# Display.net
KiCad netlist of a schematic drawn in Altium Designer
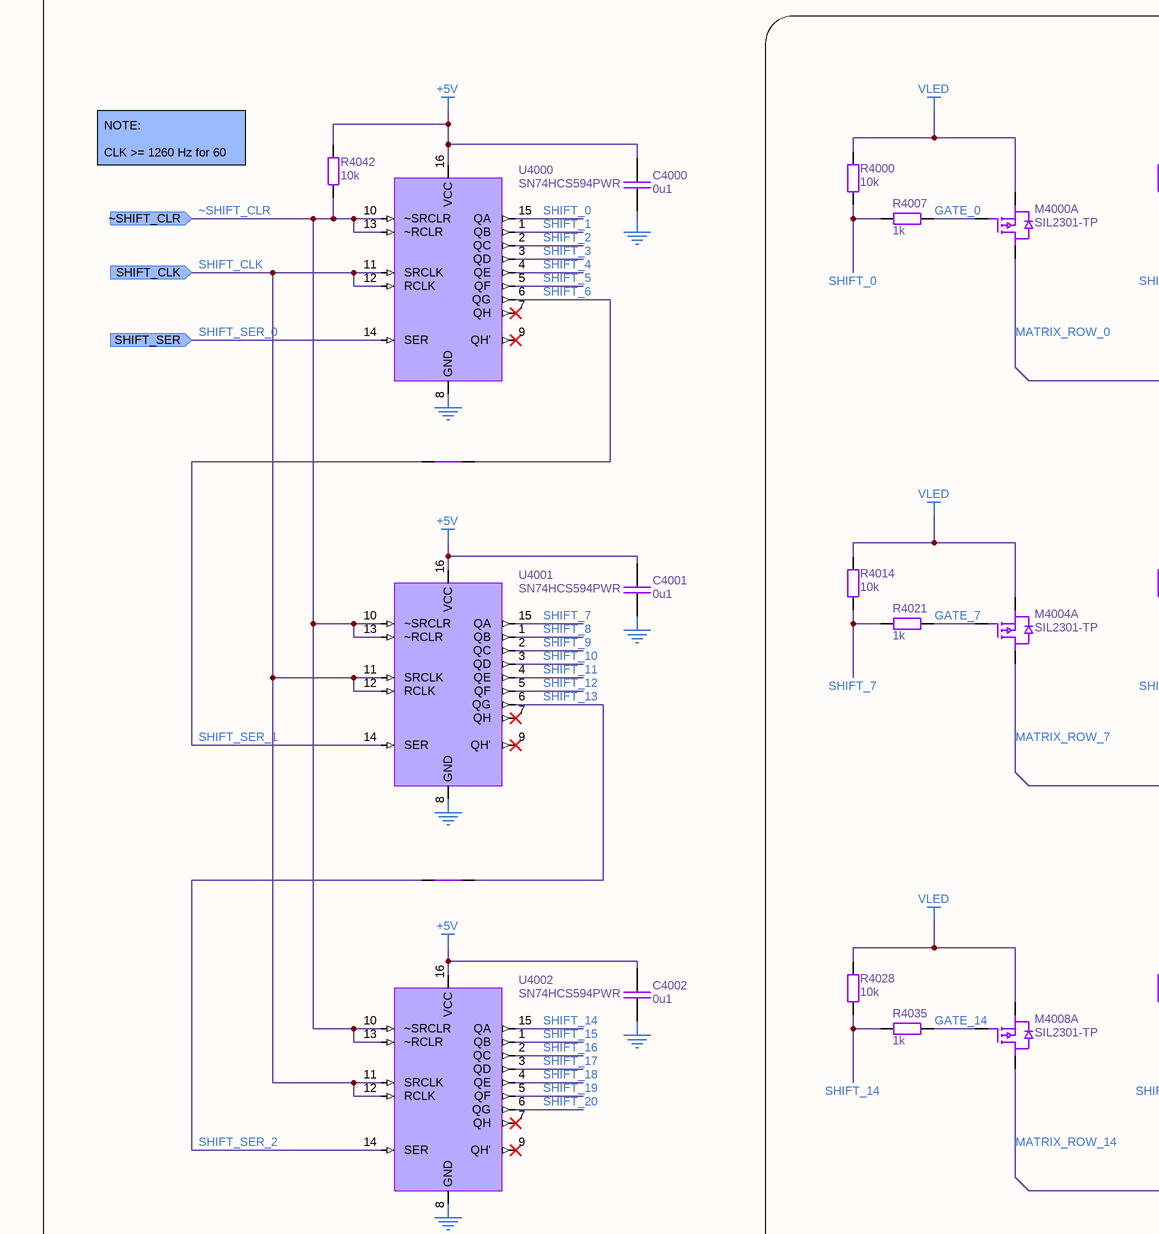
[diagram p0: Display.SchDoc, top left]
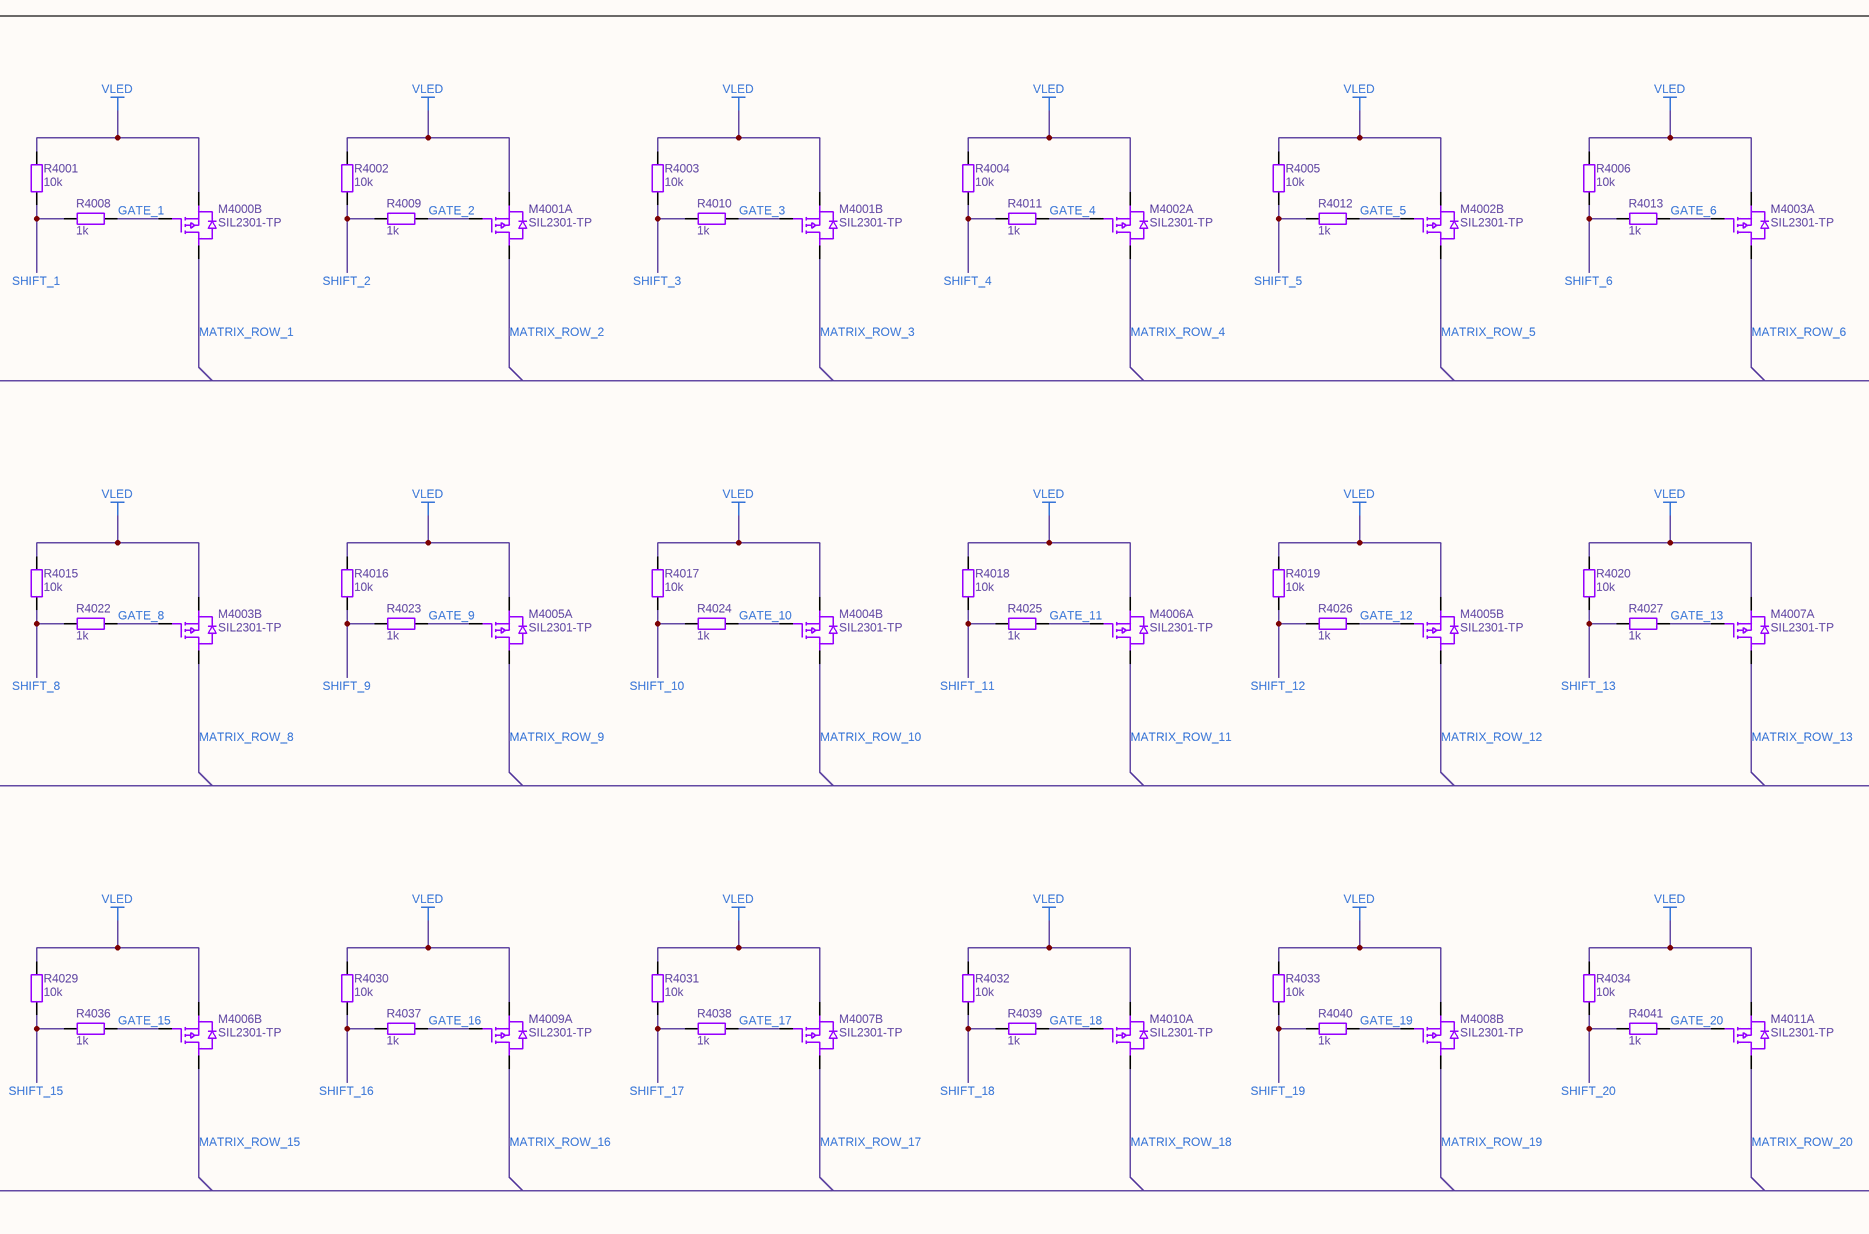
[diagram p1: Display.SchDoc, top middle]
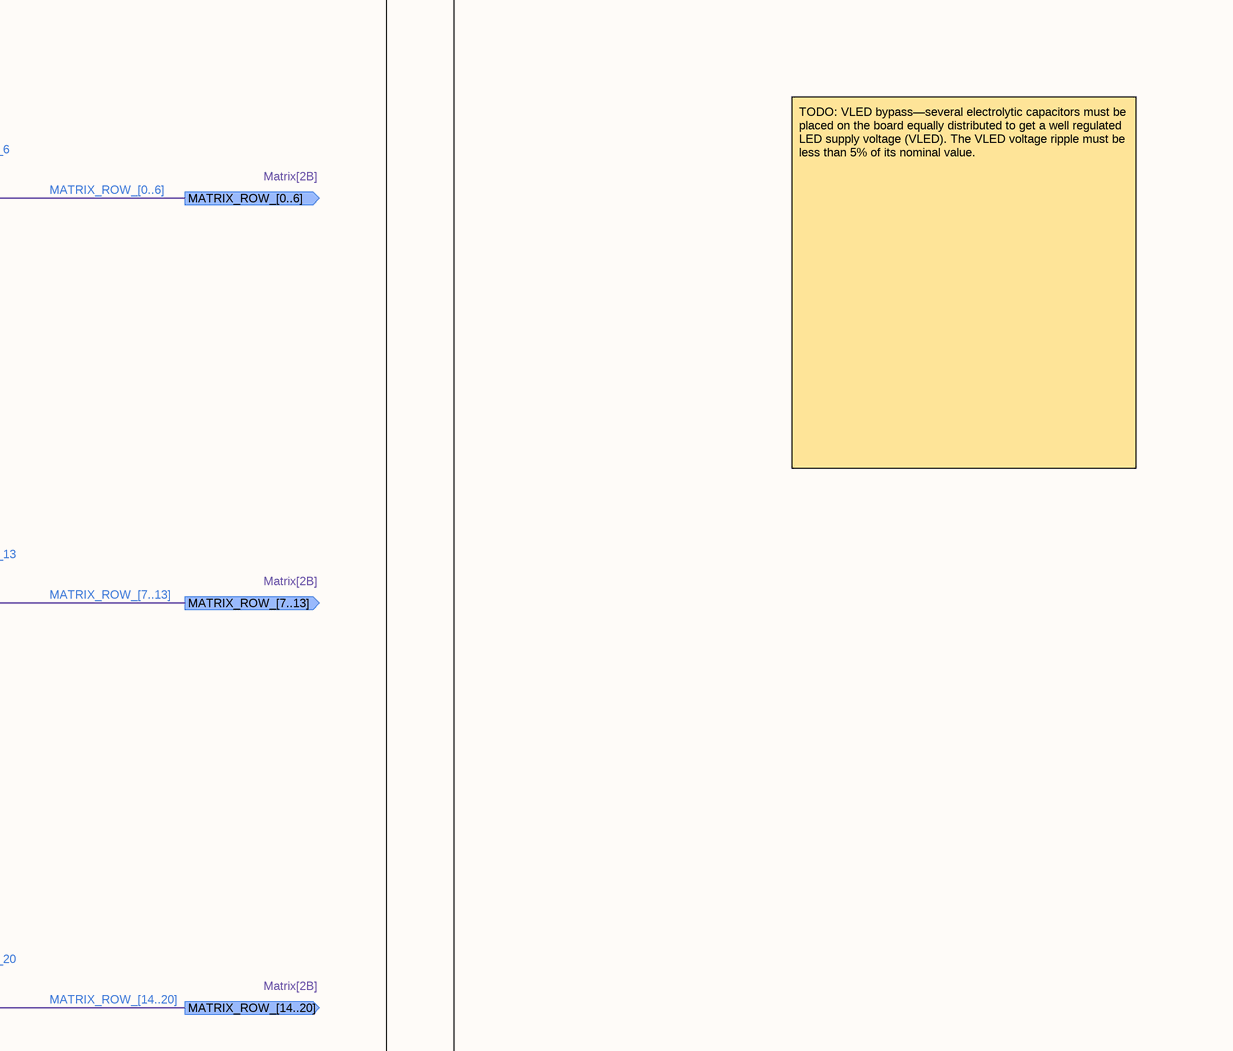
[diagram p2: Display.SchDoc, top right]
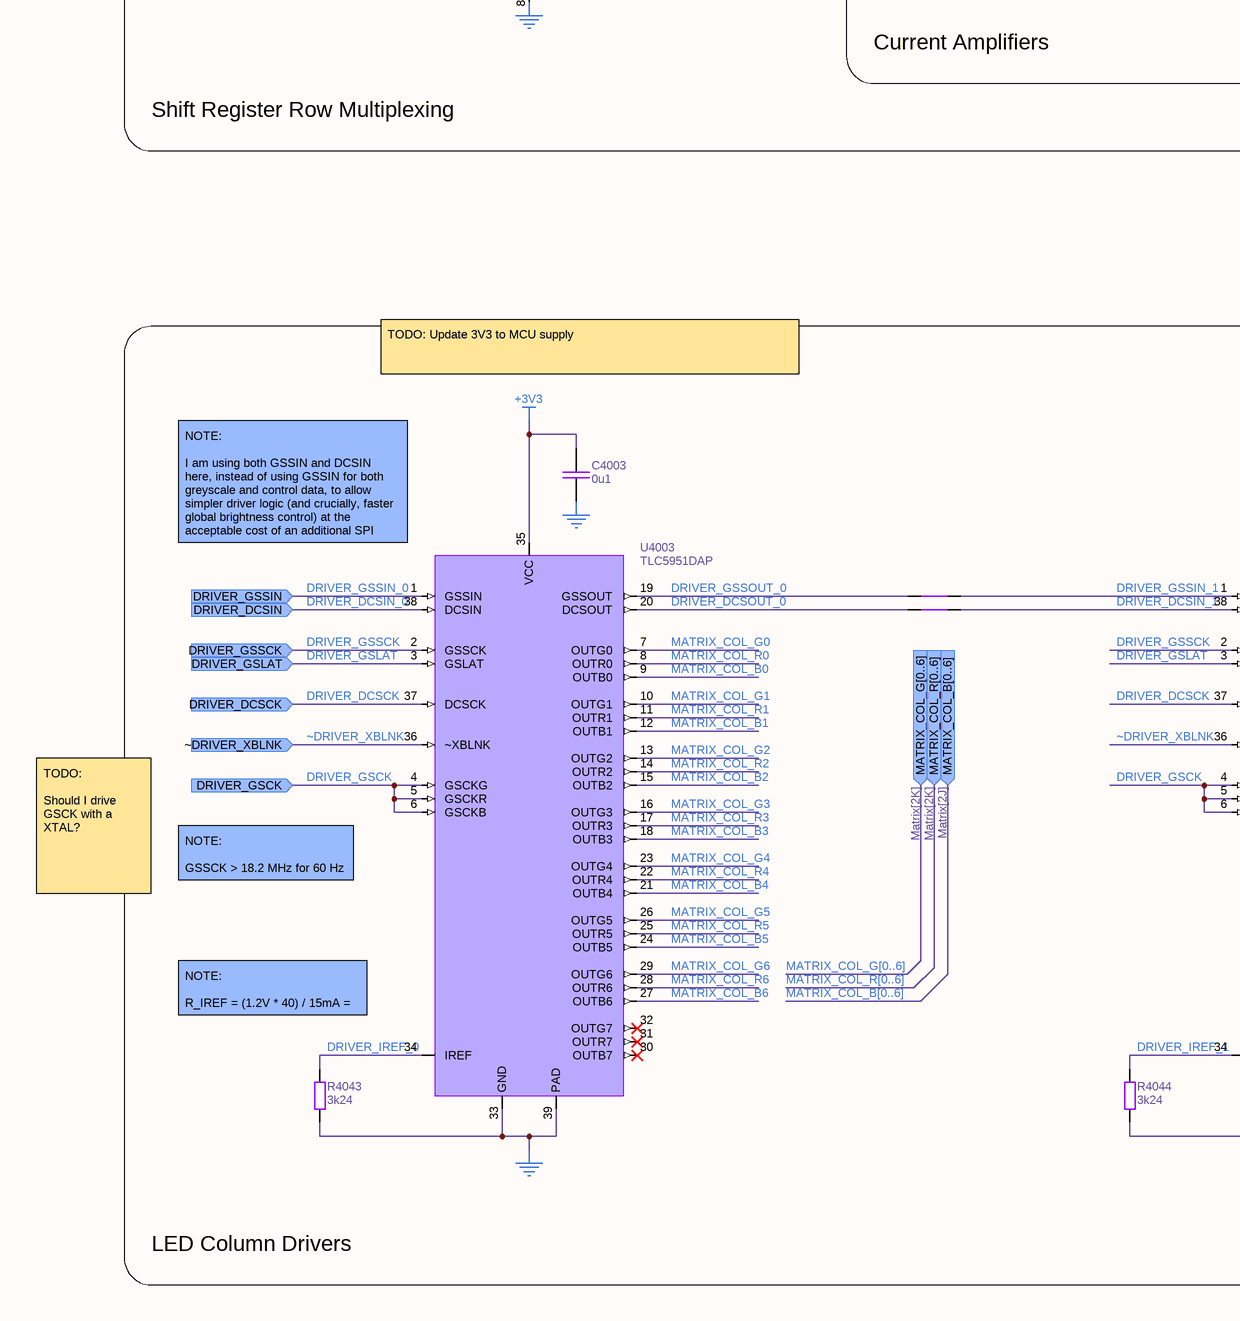
[diagram p3: Display.SchDoc, bottom left]
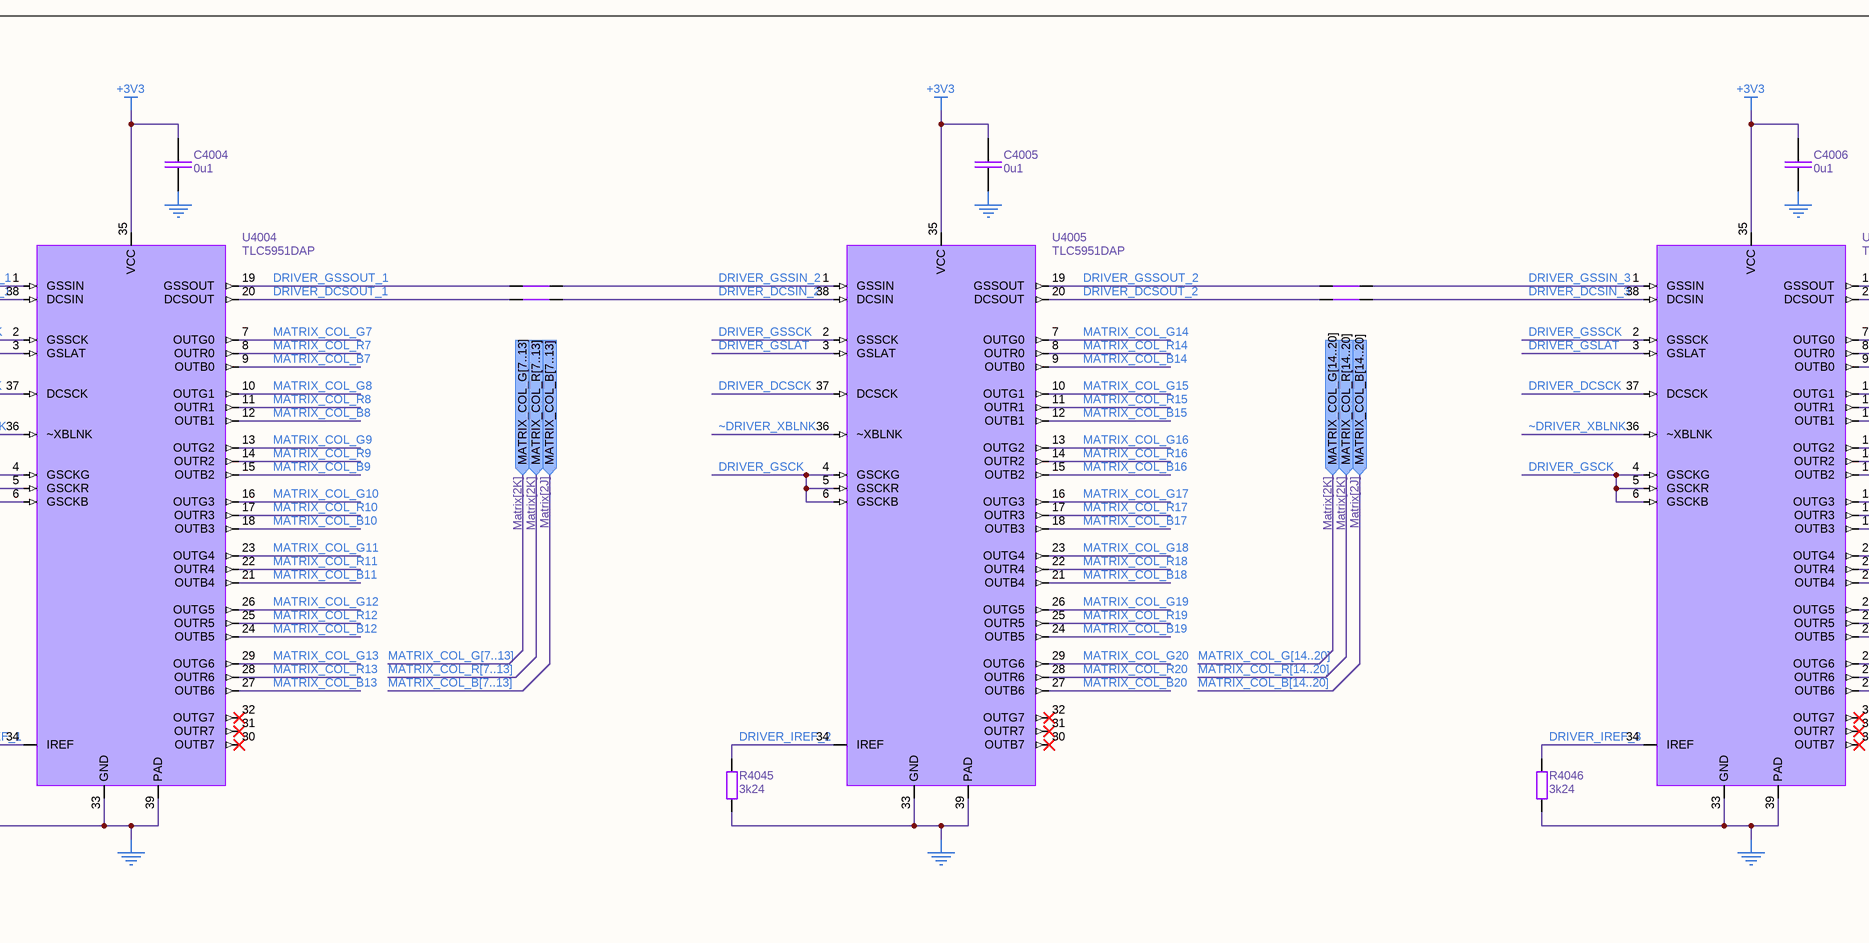
[diagram p4: Display.SchDoc, bottom middle]
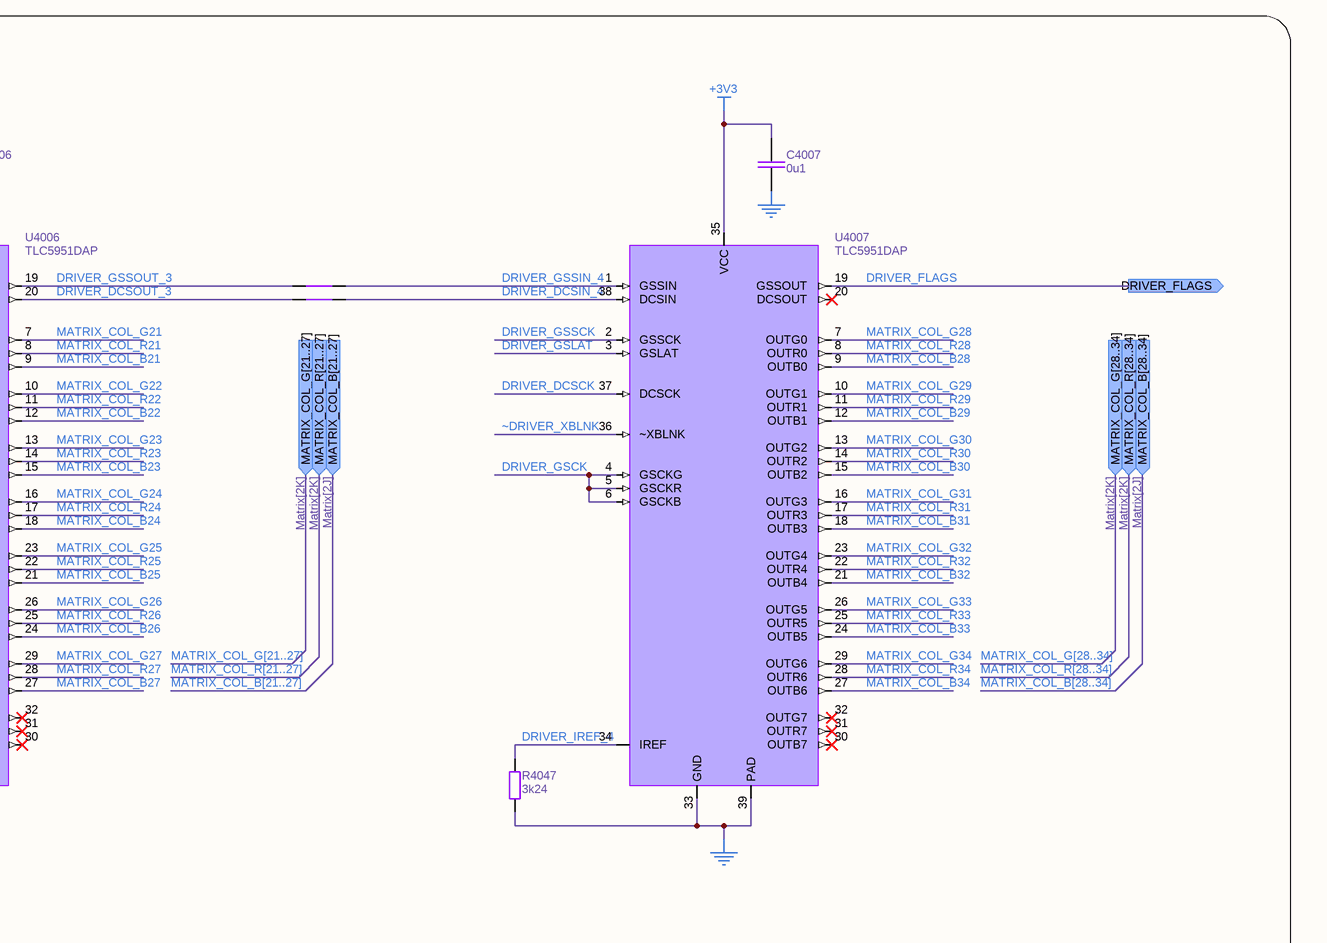
[diagram p5: Display.SchDoc, bottom right]

(export (version "E")
  (design (tool "Eeschema 10.0.6"))
  (components
    (comp (ref "C4000")
      (value "0u1")
      (footprint "CC0402KRX7R7BB104_SMT_0402")
      (description "0402 SMT 0u1 16V X7R ceramic capacitor")
      (fields
        (field (name "MANUFACTURER") "YAGEO")
        (field (name "MANUFACTURER PART NUMBER") "CC0402KRX7R7BB104")
      )
      (libsource (lib "algovision") (part "CC0402KRX7R7BB104_SMT_0402"))
    )
    (comp (ref "C4001")
      (value "0u1")
      (footprint "CC0402KRX7R7BB104_SMT_0402")
      (description "0402 SMT 0u1 16V X7R ceramic capacitor")
      (fields
        (field (name "MANUFACTURER") "YAGEO")
        (field (name "MANUFACTURER PART NUMBER") "CC0402KRX7R7BB104")
      )
      (libsource (lib "algovision") (part "CC0402KRX7R7BB104_SMT_0402"))
    )
    (comp (ref "C4002")
      (value "0u1")
      (footprint "CC0402KRX7R7BB104_SMT_0402")
      (description "0402 SMT 0u1 16V X7R ceramic capacitor")
      (fields
        (field (name "MANUFACTURER") "YAGEO")
        (field (name "MANUFACTURER PART NUMBER") "CC0402KRX7R7BB104")
      )
      (libsource (lib "algovision") (part "CC0402KRX7R7BB104_SMT_0402"))
    )
    (comp (ref "C4003")
      (value "0u1")
      (footprint "CC0402KRX7R7BB104_SMT_0402")
      (description "0402 SMT 0u1 16V X7R ceramic capacitor")
      (fields
        (field (name "MANUFACTURER") "YAGEO")
        (field (name "MANUFACTURER PART NUMBER") "CC0402KRX7R7BB104")
      )
      (libsource (lib "algovision") (part "CC0402KRX7R7BB104_SMT_0402"))
    )
    (comp (ref "C4004")
      (value "0u1")
      (footprint "CC0402KRX7R7BB104_SMT_0402")
      (description "0402 SMT 0u1 16V X7R ceramic capacitor")
      (fields
        (field (name "MANUFACTURER") "YAGEO")
        (field (name "MANUFACTURER PART NUMBER") "CC0402KRX7R7BB104")
      )
      (libsource (lib "algovision") (part "CC0402KRX7R7BB104_SMT_0402"))
    )
    (comp (ref "C4005")
      (value "0u1")
      (footprint "CC0402KRX7R7BB104_SMT_0402")
      (description "0402 SMT 0u1 16V X7R ceramic capacitor")
      (fields
        (field (name "MANUFACTURER") "YAGEO")
        (field (name "MANUFACTURER PART NUMBER") "CC0402KRX7R7BB104")
      )
      (libsource (lib "algovision") (part "CC0402KRX7R7BB104_SMT_0402"))
    )
    (comp (ref "C4006")
      (value "0u1")
      (footprint "CC0402KRX7R7BB104_SMT_0402")
      (description "0402 SMT 0u1 16V X7R ceramic capacitor")
      (fields
        (field (name "MANUFACTURER") "YAGEO")
        (field (name "MANUFACTURER PART NUMBER") "CC0402KRX7R7BB104")
      )
      (libsource (lib "algovision") (part "CC0402KRX7R7BB104_SMT_0402"))
    )
    (comp (ref "C4007")
      (value "0u1")
      (footprint "CC0402KRX7R7BB104_SMT_0402")
      (description "0402 SMT 0u1 16V X7R ceramic capacitor")
      (fields
        (field (name "MANUFACTURER") "YAGEO")
        (field (name "MANUFACTURER PART NUMBER") "CC0402KRX7R7BB104")
      )
      (libsource (lib "algovision") (part "CC0402KRX7R7BB104_SMT_0402"))
    )
    (comp (ref "M4000")
      (value "SIL2301-TP")
      (footprint "SIL2301-TP_SMT_SOT23-6L")
      (description "SOT23-6L SMT dual P-channel MOSFET")
      (fields (field (name "MANUFACTURER") "Micro Commercial Components"))
      (libsource (lib "algovision") (part "SIL2301-TP_SMT_SOT23-6L"))
    )
    (comp (ref "M4001")
      (value "SIL2301-TP")
      (footprint "SIL2301-TP_SMT_SOT23-6L")
      (description "SOT23-6L SMT dual P-channel MOSFET")
      (fields (field (name "MANUFACTURER") "Micro Commercial Components"))
      (libsource (lib "algovision") (part "SIL2301-TP_SMT_SOT23-6L"))
    )
    (comp (ref "M4002")
      (value "SIL2301-TP")
      (footprint "SIL2301-TP_SMT_SOT23-6L")
      (description "SOT23-6L SMT dual P-channel MOSFET")
      (fields (field (name "MANUFACTURER") "Micro Commercial Components"))
      (libsource (lib "algovision") (part "SIL2301-TP_SMT_SOT23-6L"))
    )
    (comp (ref "M4003")
      (value "SIL2301-TP")
      (footprint "SIL2301-TP_SMT_SOT23-6L")
      (description "SOT23-6L SMT dual P-channel MOSFET")
      (fields (field (name "MANUFACTURER") "Micro Commercial Components"))
      (libsource (lib "algovision") (part "SIL2301-TP_SMT_SOT23-6L"))
    )
    (comp (ref "M4004")
      (value "SIL2301-TP")
      (footprint "SIL2301-TP_SMT_SOT23-6L")
      (description "SOT23-6L SMT dual P-channel MOSFET")
      (fields (field (name "MANUFACTURER") "Micro Commercial Components"))
      (libsource (lib "algovision") (part "SIL2301-TP_SMT_SOT23-6L"))
    )
    (comp (ref "M4005")
      (value "SIL2301-TP")
      (footprint "SIL2301-TP_SMT_SOT23-6L")
      (description "SOT23-6L SMT dual P-channel MOSFET")
      (fields (field (name "MANUFACTURER") "Micro Commercial Components"))
      (libsource (lib "algovision") (part "SIL2301-TP_SMT_SOT23-6L"))
    )
    (comp (ref "M4006")
      (value "SIL2301-TP")
      (footprint "SIL2301-TP_SMT_SOT23-6L")
      (description "SOT23-6L SMT dual P-channel MOSFET")
      (fields (field (name "MANUFACTURER") "Micro Commercial Components"))
      (libsource (lib "algovision") (part "SIL2301-TP_SMT_SOT23-6L"))
    )
    (comp (ref "M4007")
      (value "SIL2301-TP")
      (footprint "SIL2301-TP_SMT_SOT23-6L")
      (description "SOT23-6L SMT dual P-channel MOSFET")
      (fields (field (name "MANUFACTURER") "Micro Commercial Components"))
      (libsource (lib "algovision") (part "SIL2301-TP_SMT_SOT23-6L"))
    )
    (comp (ref "M4008")
      (value "SIL2301-TP")
      (footprint "SIL2301-TP_SMT_SOT23-6L")
      (description "SOT23-6L SMT dual P-channel MOSFET")
      (fields (field (name "MANUFACTURER") "Micro Commercial Components"))
      (libsource (lib "algovision") (part "SIL2301-TP_SMT_SOT23-6L"))
    )
    (comp (ref "M4009")
      (value "SIL2301-TP")
      (footprint "SIL2301-TP_SMT_SOT23-6L")
      (description "SOT23-6L SMT dual P-channel MOSFET")
      (fields (field (name "MANUFACTURER") "Micro Commercial Components"))
      (libsource (lib "algovision") (part "SIL2301-TP_SMT_SOT23-6L"))
    )
    (comp (ref "M4010")
      (value "SIL2301-TP")
      (footprint "SIL2301-TP_SMT_SOT23-6L")
      (description "SOT23-6L SMT dual P-channel MOSFET")
      (fields (field (name "MANUFACTURER") "Micro Commercial Components"))
      (libsource (lib "algovision") (part "SIL2301-TP_SMT_SOT23-6L"))
    )
    (comp (ref "M4011")
      (value "SIL2301-TP")
      (footprint "SIL2301-TP_SMT_SOT23-6L")
      (description "SOT23-6L SMT dual P-channel MOSFET")
      (fields (field (name "MANUFACTURER") "Micro Commercial Components"))
      (libsource (lib "algovision") (part "SIL2301-TP_SMT_SOT23-6L"))
    )
    (comp (ref "NT4000")
      (value "NT")
      (footprint "NetTie_SMT")
      (description "Net Tie SMT")
      (libsource (lib "algovision") (part "NetTie_SMT"))
    )
    (comp (ref "NT4001")
      (value "NT")
      (footprint "NetTie_SMT")
      (description "Net Tie SMT")
      (libsource (lib "algovision") (part "NetTie_SMT"))
    )
    (comp (ref "NT4002")
      (value "NT")
      (footprint "NetTie_SMT")
      (description "Net Tie SMT")
      (libsource (lib "algovision") (part "NetTie_SMT"))
    )
    (comp (ref "NT4003")
      (value "NT")
      (footprint "NetTie_SMT")
      (description "Net Tie SMT")
      (libsource (lib "algovision") (part "NetTie_SMT"))
    )
    (comp (ref "NT4004")
      (value "NT")
      (footprint "NetTie_SMT")
      (description "Net Tie SMT")
      (libsource (lib "algovision") (part "NetTie_SMT"))
    )
    (comp (ref "NT4005")
      (value "NT")
      (footprint "NetTie_SMT")
      (description "Net Tie SMT")
      (libsource (lib "algovision") (part "NetTie_SMT"))
    )
    (comp (ref "NT4006")
      (value "NT")
      (footprint "NetTie_SMT")
      (description "Net Tie SMT")
      (libsource (lib "algovision") (part "NetTie_SMT"))
    )
    (comp (ref "NT4007")
      (value "NT")
      (footprint "NetTie_SMT")
      (description "Net Tie SMT")
      (libsource (lib "algovision") (part "NetTie_SMT"))
    )
    (comp (ref "NT4008")
      (value "NT")
      (footprint "NetTie_SMT")
      (description "Net Tie SMT")
      (libsource (lib "algovision") (part "NetTie_SMT"))
    )
    (comp (ref "NT4009")
      (value "NT")
      (footprint "NetTie_SMT")
      (description "Net Tie SMT")
      (libsource (lib "algovision") (part "NetTie_SMT"))
    )
    (comp (ref "R4000")
      (value "10k")
      (footprint "RC0402FR-0710KP_SMT_0402")
      (description "0402 SMT 10k chip resistor")
      (fields
        (field (name "MANUFACTURER") "YAGEO")
        (field (name "MANUFACTURER PART NUMBER") "RC0402FR-0710KP")
      )
      (libsource (lib "algovision") (part "RC0402FR-0710KP_SMT_0402"))
    )
    (comp (ref "R4001")
      (value "10k")
      (footprint "RC0402FR-0710KP_SMT_0402")
      (description "0402 SMT 10k chip resistor")
      (fields
        (field (name "MANUFACTURER") "YAGEO")
        (field (name "MANUFACTURER PART NUMBER") "RC0402FR-0710KP")
      )
      (libsource (lib "algovision") (part "RC0402FR-0710KP_SMT_0402"))
    )
    (comp (ref "R4002")
      (value "10k")
      (footprint "RC0402FR-0710KP_SMT_0402")
      (description "0402 SMT 10k chip resistor")
      (fields
        (field (name "MANUFACTURER") "YAGEO")
        (field (name "MANUFACTURER PART NUMBER") "RC0402FR-0710KP")
      )
      (libsource (lib "algovision") (part "RC0402FR-0710KP_SMT_0402"))
    )
    (comp (ref "R4003")
      (value "10k")
      (footprint "RC0402FR-0710KP_SMT_0402")
      (description "0402 SMT 10k chip resistor")
      (fields
        (field (name "MANUFACTURER") "YAGEO")
        (field (name "MANUFACTURER PART NUMBER") "RC0402FR-0710KP")
      )
      (libsource (lib "algovision") (part "RC0402FR-0710KP_SMT_0402"))
    )
    (comp (ref "R4004")
      (value "10k")
      (footprint "RC0402FR-0710KP_SMT_0402")
      (description "0402 SMT 10k chip resistor")
      (fields
        (field (name "MANUFACTURER") "YAGEO")
        (field (name "MANUFACTURER PART NUMBER") "RC0402FR-0710KP")
      )
      (libsource (lib "algovision") (part "RC0402FR-0710KP_SMT_0402"))
    )
    (comp (ref "R4005")
      (value "10k")
      (footprint "RC0402FR-0710KP_SMT_0402")
      (description "0402 SMT 10k chip resistor")
      (fields
        (field (name "MANUFACTURER") "YAGEO")
        (field (name "MANUFACTURER PART NUMBER") "RC0402FR-0710KP")
      )
      (libsource (lib "algovision") (part "RC0402FR-0710KP_SMT_0402"))
    )
    (comp (ref "R4006")
      (value "10k")
      (footprint "RC0402FR-0710KP_SMT_0402")
      (description "0402 SMT 10k chip resistor")
      (fields
        (field (name "MANUFACTURER") "YAGEO")
        (field (name "MANUFACTURER PART NUMBER") "RC0402FR-0710KP")
      )
      (libsource (lib "algovision") (part "RC0402FR-0710KP_SMT_0402"))
    )
    (comp (ref "R4007")
      (value "1k")
      (footprint "RC0402FR-071KL_SMT_0402")
      (description "0402 SMT 1k chip resistor")
      (fields
        (field (name "MANUFACTURER") "YAGEO")
        (field (name "MANUFACTURER PART NUMBER") "RC0402FR-071KL")
      )
      (libsource (lib "algovision") (part "RC0402FR-071KL_SMT_0402"))
    )
    (comp (ref "R4008")
      (value "1k")
      (footprint "RC0402FR-071KL_SMT_0402")
      (description "0402 SMT 1k chip resistor")
      (fields
        (field (name "MANUFACTURER") "YAGEO")
        (field (name "MANUFACTURER PART NUMBER") "RC0402FR-071KL")
      )
      (libsource (lib "algovision") (part "RC0402FR-071KL_SMT_0402"))
    )
    (comp (ref "R4009")
      (value "1k")
      (footprint "RC0402FR-071KL_SMT_0402")
      (description "0402 SMT 1k chip resistor")
      (fields
        (field (name "MANUFACTURER") "YAGEO")
        (field (name "MANUFACTURER PART NUMBER") "RC0402FR-071KL")
      )
      (libsource (lib "algovision") (part "RC0402FR-071KL_SMT_0402"))
    )
    (comp (ref "R4010")
      (value "1k")
      (footprint "RC0402FR-071KL_SMT_0402")
      (description "0402 SMT 1k chip resistor")
      (fields
        (field (name "MANUFACTURER") "YAGEO")
        (field (name "MANUFACTURER PART NUMBER") "RC0402FR-071KL")
      )
      (libsource (lib "algovision") (part "RC0402FR-071KL_SMT_0402"))
    )
    (comp (ref "R4011")
      (value "1k")
      (footprint "RC0402FR-071KL_SMT_0402")
      (description "0402 SMT 1k chip resistor")
      (fields
        (field (name "MANUFACTURER") "YAGEO")
        (field (name "MANUFACTURER PART NUMBER") "RC0402FR-071KL")
      )
      (libsource (lib "algovision") (part "RC0402FR-071KL_SMT_0402"))
    )
    (comp (ref "R4012")
      (value "1k")
      (footprint "RC0402FR-071KL_SMT_0402")
      (description "0402 SMT 1k chip resistor")
      (fields
        (field (name "MANUFACTURER") "YAGEO")
        (field (name "MANUFACTURER PART NUMBER") "RC0402FR-071KL")
      )
      (libsource (lib "algovision") (part "RC0402FR-071KL_SMT_0402"))
    )
    (comp (ref "R4013")
      (value "1k")
      (footprint "RC0402FR-071KL_SMT_0402")
      (description "0402 SMT 1k chip resistor")
      (fields
        (field (name "MANUFACTURER") "YAGEO")
        (field (name "MANUFACTURER PART NUMBER") "RC0402FR-071KL")
      )
      (libsource (lib "algovision") (part "RC0402FR-071KL_SMT_0402"))
    )
    (comp (ref "R4014")
      (value "10k")
      (footprint "RC0402FR-0710KP_SMT_0402")
      (description "0402 SMT 10k chip resistor")
      (fields
        (field (name "MANUFACTURER") "YAGEO")
        (field (name "MANUFACTURER PART NUMBER") "RC0402FR-0710KP")
      )
      (libsource (lib "algovision") (part "RC0402FR-0710KP_SMT_0402"))
    )
    (comp (ref "R4015")
      (value "10k")
      (footprint "RC0402FR-0710KP_SMT_0402")
      (description "0402 SMT 10k chip resistor")
      (fields
        (field (name "MANUFACTURER") "YAGEO")
        (field (name "MANUFACTURER PART NUMBER") "RC0402FR-0710KP")
      )
      (libsource (lib "algovision") (part "RC0402FR-0710KP_SMT_0402"))
    )
    (comp (ref "R4016")
      (value "10k")
      (footprint "RC0402FR-0710KP_SMT_0402")
      (description "0402 SMT 10k chip resistor")
      (fields
        (field (name "MANUFACTURER") "YAGEO")
        (field (name "MANUFACTURER PART NUMBER") "RC0402FR-0710KP")
      )
      (libsource (lib "algovision") (part "RC0402FR-0710KP_SMT_0402"))
    )
    (comp (ref "R4017")
      (value "10k")
      (footprint "RC0402FR-0710KP_SMT_0402")
      (description "0402 SMT 10k chip resistor")
      (fields
        (field (name "MANUFACTURER") "YAGEO")
        (field (name "MANUFACTURER PART NUMBER") "RC0402FR-0710KP")
      )
      (libsource (lib "algovision") (part "RC0402FR-0710KP_SMT_0402"))
    )
    (comp (ref "R4018")
      (value "10k")
      (footprint "RC0402FR-0710KP_SMT_0402")
      (description "0402 SMT 10k chip resistor")
      (fields
        (field (name "MANUFACTURER") "YAGEO")
        (field (name "MANUFACTURER PART NUMBER") "RC0402FR-0710KP")
      )
      (libsource (lib "algovision") (part "RC0402FR-0710KP_SMT_0402"))
    )
    (comp (ref "R4019")
      (value "10k")
      (footprint "RC0402FR-0710KP_SMT_0402")
      (description "0402 SMT 10k chip resistor")
      (fields
        (field (name "MANUFACTURER") "YAGEO")
        (field (name "MANUFACTURER PART NUMBER") "RC0402FR-0710KP")
      )
      (libsource (lib "algovision") (part "RC0402FR-0710KP_SMT_0402"))
    )
    (comp (ref "R4020")
      (value "10k")
      (footprint "RC0402FR-0710KP_SMT_0402")
      (description "0402 SMT 10k chip resistor")
      (fields
        (field (name "MANUFACTURER") "YAGEO")
        (field (name "MANUFACTURER PART NUMBER") "RC0402FR-0710KP")
      )
      (libsource (lib "algovision") (part "RC0402FR-0710KP_SMT_0402"))
    )
    (comp (ref "R4021")
      (value "1k")
      (footprint "RC0402FR-071KL_SMT_0402")
      (description "0402 SMT 1k chip resistor")
      (fields
        (field (name "MANUFACTURER") "YAGEO")
        (field (name "MANUFACTURER PART NUMBER") "RC0402FR-071KL")
      )
      (libsource (lib "algovision") (part "RC0402FR-071KL_SMT_0402"))
    )
    (comp (ref "R4022")
      (value "1k")
      (footprint "RC0402FR-071KL_SMT_0402")
      (description "0402 SMT 1k chip resistor")
      (fields
        (field (name "MANUFACTURER") "YAGEO")
        (field (name "MANUFACTURER PART NUMBER") "RC0402FR-071KL")
      )
      (libsource (lib "algovision") (part "RC0402FR-071KL_SMT_0402"))
    )
    (comp (ref "R4023")
      (value "1k")
      (footprint "RC0402FR-071KL_SMT_0402")
      (description "0402 SMT 1k chip resistor")
      (fields
        (field (name "MANUFACTURER") "YAGEO")
        (field (name "MANUFACTURER PART NUMBER") "RC0402FR-071KL")
      )
      (libsource (lib "algovision") (part "RC0402FR-071KL_SMT_0402"))
    )
    (comp (ref "R4024")
      (value "1k")
      (footprint "RC0402FR-071KL_SMT_0402")
      (description "0402 SMT 1k chip resistor")
      (fields
        (field (name "MANUFACTURER") "YAGEO")
        (field (name "MANUFACTURER PART NUMBER") "RC0402FR-071KL")
      )
      (libsource (lib "algovision") (part "RC0402FR-071KL_SMT_0402"))
    )
    (comp (ref "R4025")
      (value "1k")
      (footprint "RC0402FR-071KL_SMT_0402")
      (description "0402 SMT 1k chip resistor")
      (fields
        (field (name "MANUFACTURER") "YAGEO")
        (field (name "MANUFACTURER PART NUMBER") "RC0402FR-071KL")
      )
      (libsource (lib "algovision") (part "RC0402FR-071KL_SMT_0402"))
    )
    (comp (ref "R4026")
      (value "1k")
      (footprint "RC0402FR-071KL_SMT_0402")
      (description "0402 SMT 1k chip resistor")
      (fields
        (field (name "MANUFACTURER") "YAGEO")
        (field (name "MANUFACTURER PART NUMBER") "RC0402FR-071KL")
      )
      (libsource (lib "algovision") (part "RC0402FR-071KL_SMT_0402"))
    )
    (comp (ref "R4027")
      (value "1k")
      (footprint "RC0402FR-071KL_SMT_0402")
      (description "0402 SMT 1k chip resistor")
      (fields
        (field (name "MANUFACTURER") "YAGEO")
        (field (name "MANUFACTURER PART NUMBER") "RC0402FR-071KL")
      )
      (libsource (lib "algovision") (part "RC0402FR-071KL_SMT_0402"))
    )
    (comp (ref "R4028")
      (value "10k")
      (footprint "RC0402FR-0710KP_SMT_0402")
      (description "0402 SMT 10k chip resistor")
      (fields
        (field (name "MANUFACTURER") "YAGEO")
        (field (name "MANUFACTURER PART NUMBER") "RC0402FR-0710KP")
      )
      (libsource (lib "algovision") (part "RC0402FR-0710KP_SMT_0402"))
    )
    (comp (ref "R4029")
      (value "10k")
      (footprint "RC0402FR-0710KP_SMT_0402")
      (description "0402 SMT 10k chip resistor")
      (fields
        (field (name "MANUFACTURER") "YAGEO")
        (field (name "MANUFACTURER PART NUMBER") "RC0402FR-0710KP")
      )
      (libsource (lib "algovision") (part "RC0402FR-0710KP_SMT_0402"))
    )
    (comp (ref "R4030")
      (value "10k")
      (footprint "RC0402FR-0710KP_SMT_0402")
      (description "0402 SMT 10k chip resistor")
      (fields
        (field (name "MANUFACTURER") "YAGEO")
        (field (name "MANUFACTURER PART NUMBER") "RC0402FR-0710KP")
      )
      (libsource (lib "algovision") (part "RC0402FR-0710KP_SMT_0402"))
    )
    (comp (ref "R4031")
      (value "10k")
      (footprint "RC0402FR-0710KP_SMT_0402")
      (description "0402 SMT 10k chip resistor")
      (fields
        (field (name "MANUFACTURER") "YAGEO")
        (field (name "MANUFACTURER PART NUMBER") "RC0402FR-0710KP")
      )
      (libsource (lib "algovision") (part "RC0402FR-0710KP_SMT_0402"))
    )
    (comp (ref "R4032")
      (value "10k")
      (footprint "RC0402FR-0710KP_SMT_0402")
      (description "0402 SMT 10k chip resistor")
      (fields
        (field (name "MANUFACTURER") "YAGEO")
        (field (name "MANUFACTURER PART NUMBER") "RC0402FR-0710KP")
      )
      (libsource (lib "algovision") (part "RC0402FR-0710KP_SMT_0402"))
    )
    (comp (ref "R4033")
      (value "10k")
      (footprint "RC0402FR-0710KP_SMT_0402")
      (description "0402 SMT 10k chip resistor")
      (fields
        (field (name "MANUFACTURER") "YAGEO")
        (field (name "MANUFACTURER PART NUMBER") "RC0402FR-0710KP")
      )
      (libsource (lib "algovision") (part "RC0402FR-0710KP_SMT_0402"))
    )
    (comp (ref "R4034")
      (value "10k")
      (footprint "RC0402FR-0710KP_SMT_0402")
      (description "0402 SMT 10k chip resistor")
      (fields
        (field (name "MANUFACTURER") "YAGEO")
        (field (name "MANUFACTURER PART NUMBER") "RC0402FR-0710KP")
      )
      (libsource (lib "algovision") (part "RC0402FR-0710KP_SMT_0402"))
    )
    (comp (ref "R4035")
      (value "1k")
      (footprint "RC0402FR-071KL_SMT_0402")
      (description "0402 SMT 1k chip resistor")
      (fields
        (field (name "MANUFACTURER") "YAGEO")
        (field (name "MANUFACTURER PART NUMBER") "RC0402FR-071KL")
      )
      (libsource (lib "algovision") (part "RC0402FR-071KL_SMT_0402"))
    )
    (comp (ref "R4036")
      (value "1k")
      (footprint "RC0402FR-071KL_SMT_0402")
      (description "0402 SMT 1k chip resistor")
      (fields
        (field (name "MANUFACTURER") "YAGEO")
        (field (name "MANUFACTURER PART NUMBER") "RC0402FR-071KL")
      )
      (libsource (lib "algovision") (part "RC0402FR-071KL_SMT_0402"))
    )
    (comp (ref "R4037")
      (value "1k")
      (footprint "RC0402FR-071KL_SMT_0402")
      (description "0402 SMT 1k chip resistor")
      (fields
        (field (name "MANUFACTURER") "YAGEO")
        (field (name "MANUFACTURER PART NUMBER") "RC0402FR-071KL")
      )
      (libsource (lib "algovision") (part "RC0402FR-071KL_SMT_0402"))
    )
    (comp (ref "R4038")
      (value "1k")
      (footprint "RC0402FR-071KL_SMT_0402")
      (description "0402 SMT 1k chip resistor")
      (fields
        (field (name "MANUFACTURER") "YAGEO")
        (field (name "MANUFACTURER PART NUMBER") "RC0402FR-071KL")
      )
      (libsource (lib "algovision") (part "RC0402FR-071KL_SMT_0402"))
    )
    (comp (ref "R4039")
      (value "1k")
      (footprint "RC0402FR-071KL_SMT_0402")
      (description "0402 SMT 1k chip resistor")
      (fields
        (field (name "MANUFACTURER") "YAGEO")
        (field (name "MANUFACTURER PART NUMBER") "RC0402FR-071KL")
      )
      (libsource (lib "algovision") (part "RC0402FR-071KL_SMT_0402"))
    )
    (comp (ref "R4040")
      (value "1k")
      (footprint "RC0402FR-071KL_SMT_0402")
      (description "0402 SMT 1k chip resistor")
      (fields
        (field (name "MANUFACTURER") "YAGEO")
        (field (name "MANUFACTURER PART NUMBER") "RC0402FR-071KL")
      )
      (libsource (lib "algovision") (part "RC0402FR-071KL_SMT_0402"))
    )
    (comp (ref "R4041")
      (value "1k")
      (footprint "RC0402FR-071KL_SMT_0402")
      (description "0402 SMT 1k chip resistor")
      (fields
        (field (name "MANUFACTURER") "YAGEO")
        (field (name "MANUFACTURER PART NUMBER") "RC0402FR-071KL")
      )
      (libsource (lib "algovision") (part "RC0402FR-071KL_SMT_0402"))
    )
    (comp (ref "R4042")
      (value "10k")
      (footprint "RC0402FR-0710KP_SMT_0402")
      (description "0402 SMT 10k chip resistor")
      (fields
        (field (name "MANUFACTURER") "YAGEO")
        (field (name "MANUFACTURER PART NUMBER") "RC0402FR-0710KP")
      )
      (libsource (lib "algovision") (part "RC0402FR-0710KP_SMT_0402"))
    )
    (comp (ref "R4043")
      (value "3k24")
      (footprint "RC0402FR-073K24L_SMT_0402")
      (description "0402 SMT 3k24 chip resistor")
      (fields
        (field (name "MANUFACTURER") "YAGEO")
        (field (name "MANUFACTURER PART NUMBER") "RC0402FR-073K24L")
      )
      (libsource (lib "algovision") (part "RC0402FR-073K24L_SMT_0402"))
    )
    (comp (ref "R4044")
      (value "3k24")
      (footprint "RC0402FR-073K24L_SMT_0402")
      (description "0402 SMT 3k24 chip resistor")
      (fields
        (field (name "MANUFACTURER") "YAGEO")
        (field (name "MANUFACTURER PART NUMBER") "RC0402FR-073K24L")
      )
      (libsource (lib "algovision") (part "RC0402FR-073K24L_SMT_0402"))
    )
    (comp (ref "R4045")
      (value "3k24")
      (footprint "RC0402FR-073K24L_SMT_0402")
      (description "0402 SMT 3k24 chip resistor")
      (fields
        (field (name "MANUFACTURER") "YAGEO")
        (field (name "MANUFACTURER PART NUMBER") "RC0402FR-073K24L")
      )
      (libsource (lib "algovision") (part "RC0402FR-073K24L_SMT_0402"))
    )
    (comp (ref "R4046")
      (value "3k24")
      (footprint "RC0402FR-073K24L_SMT_0402")
      (description "0402 SMT 3k24 chip resistor")
      (fields
        (field (name "MANUFACTURER") "YAGEO")
        (field (name "MANUFACTURER PART NUMBER") "RC0402FR-073K24L")
      )
      (libsource (lib "algovision") (part "RC0402FR-073K24L_SMT_0402"))
    )
    (comp (ref "R4047")
      (value "3k24")
      (footprint "RC0402FR-073K24L_SMT_0402")
      (description "0402 SMT 3k24 chip resistor")
      (fields
        (field (name "MANUFACTURER") "YAGEO")
        (field (name "MANUFACTURER PART NUMBER") "RC0402FR-073K24L")
      )
      (libsource (lib "algovision") (part "RC0402FR-073K24L_SMT_0402"))
    )
    (comp (ref "U4000")
      (value "SN74HCS594PWR")
      (footprint "SN74HCS594PWR_SMT_16-TSSOP")
      (description "16-TSSOP SMT 8 bit shift register")
      (fields (field (name "MANUFACTURER") "Texas Instruments"))
      (libsource (lib "algovision") (part "SN74HCS594PWR_SMT_16-TSSPOP"))
    )
    (comp (ref "U4001")
      (value "SN74HCS594PWR")
      (footprint "SN74HCS594PWR_SMT_16-TSSOP")
      (description "16-TSSOP SMT 8 bit shift register")
      (fields (field (name "MANUFACTURER") "Texas Instruments"))
      (libsource (lib "algovision") (part "SN74HCS594PWR_SMT_16-TSSPOP"))
    )
    (comp (ref "U4002")
      (value "SN74HCS594PWR")
      (footprint "SN74HCS594PWR_SMT_16-TSSOP")
      (description "16-TSSOP SMT 8 bit shift register")
      (fields (field (name "MANUFACTURER") "Texas Instruments"))
      (libsource (lib "algovision") (part "SN74HCS594PWR_SMT_16-TSSPOP"))
    )
    (comp (ref "U4003")
      (value "TLC5951DAP")
      (footprint "TLC5951DAP_SMT_38-HTSSOP")
      (description "38-HTSSOP SMT 24 output linear shift register LED driver")
      (fields (field (name "MANUFACTURER") "Texas Instruments"))
      (libsource (lib "algovision") (part "TLC5951DAP_SMT_38-HTSSOP"))
    )
    (comp (ref "U4004")
      (value "TLC5951DAP")
      (footprint "TLC5951DAP_SMT_38-HTSSOP")
      (description "38-HTSSOP SMT 24 output linear shift register LED driver")
      (fields (field (name "MANUFACTURER") "Texas Instruments"))
      (libsource (lib "algovision") (part "TLC5951DAP_SMT_38-HTSSOP"))
    )
    (comp (ref "U4005")
      (value "TLC5951DAP")
      (footprint "TLC5951DAP_SMT_38-HTSSOP")
      (description "38-HTSSOP SMT 24 output linear shift register LED driver")
      (fields (field (name "MANUFACTURER") "Texas Instruments"))
      (libsource (lib "algovision") (part "TLC5951DAP_SMT_38-HTSSOP"))
    )
    (comp (ref "U4006")
      (value "TLC5951DAP")
      (footprint "TLC5951DAP_SMT_38-HTSSOP")
      (description "38-HTSSOP SMT 24 output linear shift register LED driver")
      (fields (field (name "MANUFACTURER") "Texas Instruments"))
      (libsource (lib "algovision") (part "TLC5951DAP_SMT_38-HTSSOP"))
    )
    (comp (ref "U4007")
      (value "TLC5951DAP")
      (footprint "TLC5951DAP_SMT_38-HTSSOP")
      (description "38-HTSSOP SMT 24 output linear shift register LED driver")
      (fields (field (name "MANUFACTURER") "Texas Instruments"))
      (libsource (lib "algovision") (part "TLC5951DAP_SMT_38-HTSSOP"))
    )
  )
  (nets
    (net (code "1") (name "+3V3") (class "Default")
      (node (ref "C4003") (pin "2") (pinfunction "2_2") (pintype "passive"))
      (node (ref "C4004") (pin "2") (pinfunction "2_2") (pintype "passive"))
      (node (ref "C4005") (pin "2") (pinfunction "2_2") (pintype "passive"))
      (node (ref "C4006") (pin "2") (pinfunction "2_2") (pintype "passive"))
      (node (ref "C4007") (pin "2") (pinfunction "2_2") (pintype "passive"))
      (node (ref "U4003") (pin "35") (pinfunction "VCC_35") (pintype "power_in"))
      (node (ref "U4004") (pin "35") (pinfunction "VCC_35") (pintype "power_in"))
      (node (ref "U4005") (pin "35") (pinfunction "VCC_35") (pintype "power_in"))
      (node (ref "U4006") (pin "35") (pinfunction "VCC_35") (pintype "power_in"))
      (node (ref "U4007") (pin "35") (pinfunction "VCC_35") (pintype "power_in"))
    )
    (net (code "2") (name "+5V") (class "Default")
      (node (ref "C4000") (pin "2") (pinfunction "2_2") (pintype "passive"))
      (node (ref "C4001") (pin "2") (pinfunction "2_2") (pintype "passive"))
      (node (ref "C4002") (pin "2") (pinfunction "2_2") (pintype "passive"))
      (node (ref "R4042") (pin "2") (pinfunction "2_2") (pintype "passive"))
      (node (ref "U4000") (pin "16") (pinfunction "VCC_16") (pintype "power_in"))
      (node (ref "U4001") (pin "16") (pinfunction "VCC_16") (pintype "power_in"))
      (node (ref "U4002") (pin "16") (pinfunction "VCC_16") (pintype "power_in"))
    )
    (net (code "3") (name "/DRIVER_DCSCK") (class "Default")
      (node (ref "U4003") (pin "37") (pinfunction "DCSCK_37") (pintype "input"))
      (node (ref "U4004") (pin "37") (pinfunction "DCSCK_37") (pintype "input"))
      (node (ref "U4005") (pin "37") (pinfunction "DCSCK_37") (pintype "input"))
      (node (ref "U4006") (pin "37") (pinfunction "DCSCK_37") (pintype "input"))
      (node (ref "U4007") (pin "37") (pinfunction "DCSCK_37") (pintype "input"))
    )
    (net (code "4") (name "/DRIVER_DCSIN_0") (class "Default")
      (node (ref "U4003") (pin "38") (pinfunction "DCSIN_38") (pintype "input"))
    )
    (net (code "5") (name "/DRIVER_DCSIN_1") (class "Default")
      (node (ref "NT4004") (pin "2") (pinfunction "2_2") (pintype "passive"))
      (node (ref "U4004") (pin "38") (pinfunction "DCSIN_38") (pintype "input"))
    )
    (net (code "6") (name "/DRIVER_DCSIN_2") (class "Default")
      (node (ref "NT4005") (pin "2") (pinfunction "2_2") (pintype "passive"))
      (node (ref "U4005") (pin "38") (pinfunction "DCSIN_38") (pintype "input"))
    )
    (net (code "7") (name "/DRIVER_DCSIN_3") (class "Default")
      (node (ref "NT4006") (pin "2") (pinfunction "2_2") (pintype "passive"))
      (node (ref "U4006") (pin "38") (pinfunction "DCSIN_38") (pintype "input"))
    )
    (net (code "8") (name "/DRIVER_DCSIN_4") (class "Default")
      (node (ref "NT4007") (pin "2") (pinfunction "2_2") (pintype "passive"))
      (node (ref "U4007") (pin "38") (pinfunction "DCSIN_38") (pintype "input"))
    )
    (net (code "9") (name "/DRIVER_DCSOUT_0") (class "Default")
      (node (ref "NT4004") (pin "1") (pinfunction "1_1") (pintype "passive"))
      (node (ref "U4003") (pin "20") (pinfunction "DCSOUT_20") (pintype "output"))
    )
    (net (code "10") (name "/DRIVER_DCSOUT_1") (class "Default")
      (node (ref "NT4005") (pin "1") (pinfunction "1_1") (pintype "passive"))
      (node (ref "U4004") (pin "20") (pinfunction "DCSOUT_20") (pintype "output"))
    )
    (net (code "11") (name "/DRIVER_DCSOUT_2") (class "Default")
      (node (ref "NT4006") (pin "1") (pinfunction "1_1") (pintype "passive"))
      (node (ref "U4005") (pin "20") (pinfunction "DCSOUT_20") (pintype "output"))
    )
    (net (code "12") (name "/DRIVER_DCSOUT_3") (class "Default")
      (node (ref "NT4007") (pin "1") (pinfunction "1_1") (pintype "passive"))
      (node (ref "U4006") (pin "20") (pinfunction "DCSOUT_20") (pintype "output"))
    )
    (net (code "13") (name "/DRIVER_FLAGS") (class "Default")
      (node (ref "U4007") (pin "19") (pinfunction "GSSOUT_19") (pintype "output"))
    )
    (net (code "14") (name "/DRIVER_GSCK") (class "Default")
      (node (ref "U4003") (pin "4") (pinfunction "GSCKG_4") (pintype "input"))
      (node (ref "U4003") (pin "5") (pinfunction "GSCKR_5") (pintype "input"))
      (node (ref "U4003") (pin "6") (pinfunction "GSCKB_6") (pintype "input"))
      (node (ref "U4004") (pin "4") (pinfunction "GSCKG_4") (pintype "input"))
      (node (ref "U4004") (pin "5") (pinfunction "GSCKR_5") (pintype "input"))
      (node (ref "U4004") (pin "6") (pinfunction "GSCKB_6") (pintype "input"))
      (node (ref "U4005") (pin "4") (pinfunction "GSCKG_4") (pintype "input"))
      (node (ref "U4005") (pin "5") (pinfunction "GSCKR_5") (pintype "input"))
      (node (ref "U4005") (pin "6") (pinfunction "GSCKB_6") (pintype "input"))
      (node (ref "U4006") (pin "4") (pinfunction "GSCKG_4") (pintype "input"))
      (node (ref "U4006") (pin "5") (pinfunction "GSCKR_5") (pintype "input"))
      (node (ref "U4006") (pin "6") (pinfunction "GSCKB_6") (pintype "input"))
      (node (ref "U4007") (pin "4") (pinfunction "GSCKG_4") (pintype "input"))
      (node (ref "U4007") (pin "5") (pinfunction "GSCKR_5") (pintype "input"))
      (node (ref "U4007") (pin "6") (pinfunction "GSCKB_6") (pintype "input"))
    )
    (net (code "15") (name "/DRIVER_GSLAT") (class "Default")
      (node (ref "U4003") (pin "3") (pinfunction "GSLAT_3") (pintype "input"))
      (node (ref "U4004") (pin "3") (pinfunction "GSLAT_3") (pintype "input"))
      (node (ref "U4005") (pin "3") (pinfunction "GSLAT_3") (pintype "input"))
      (node (ref "U4006") (pin "3") (pinfunction "GSLAT_3") (pintype "input"))
      (node (ref "U4007") (pin "3") (pinfunction "GSLAT_3") (pintype "input"))
    )
    (net (code "16") (name "/DRIVER_GSSCK") (class "Default")
      (node (ref "U4003") (pin "2") (pinfunction "GSSCK_2") (pintype "input"))
      (node (ref "U4004") (pin "2") (pinfunction "GSSCK_2") (pintype "input"))
      (node (ref "U4005") (pin "2") (pinfunction "GSSCK_2") (pintype "input"))
      (node (ref "U4006") (pin "2") (pinfunction "GSSCK_2") (pintype "input"))
      (node (ref "U4007") (pin "2") (pinfunction "GSSCK_2") (pintype "input"))
    )
    (net (code "17") (name "/DRIVER_GSSIN_0") (class "Default")
      (node (ref "U4003") (pin "1") (pinfunction "GSSIN_1") (pintype "input"))
    )
    (net (code "18") (name "/DRIVER_GSSIN_1") (class "Default")
      (node (ref "NT4000") (pin "2") (pinfunction "2_2") (pintype "passive"))
      (node (ref "U4004") (pin "1") (pinfunction "GSSIN_1") (pintype "input"))
    )
    (net (code "19") (name "/DRIVER_GSSIN_2") (class "Default")
      (node (ref "NT4001") (pin "2") (pinfunction "2_2") (pintype "passive"))
      (node (ref "U4005") (pin "1") (pinfunction "GSSIN_1") (pintype "input"))
    )
    (net (code "20") (name "/DRIVER_GSSIN_3") (class "Default")
      (node (ref "NT4002") (pin "2") (pinfunction "2_2") (pintype "passive"))
      (node (ref "U4006") (pin "1") (pinfunction "GSSIN_1") (pintype "input"))
    )
    (net (code "21") (name "/DRIVER_GSSIN_4") (class "Default")
      (node (ref "NT4003") (pin "2") (pinfunction "2_2") (pintype "passive"))
      (node (ref "U4007") (pin "1") (pinfunction "GSSIN_1") (pintype "input"))
    )
    (net (code "22") (name "/DRIVER_GSSOUT_0") (class "Default")
      (node (ref "NT4000") (pin "1") (pinfunction "1_1") (pintype "passive"))
      (node (ref "U4003") (pin "19") (pinfunction "GSSOUT_19") (pintype "output"))
    )
    (net (code "23") (name "/DRIVER_GSSOUT_1") (class "Default")
      (node (ref "NT4001") (pin "1") (pinfunction "1_1") (pintype "passive"))
      (node (ref "U4004") (pin "19") (pinfunction "GSSOUT_19") (pintype "output"))
    )
    (net (code "24") (name "/DRIVER_GSSOUT_2") (class "Default")
      (node (ref "NT4002") (pin "1") (pinfunction "1_1") (pintype "passive"))
      (node (ref "U4005") (pin "19") (pinfunction "GSSOUT_19") (pintype "output"))
    )
    (net (code "25") (name "/DRIVER_GSSOUT_3") (class "Default")
      (node (ref "NT4003") (pin "1") (pinfunction "1_1") (pintype "passive"))
      (node (ref "U4006") (pin "19") (pinfunction "GSSOUT_19") (pintype "output"))
    )
    (net (code "26") (name "/DRIVER_IREF_0") (class "Default")
      (node (ref "R4043") (pin "2") (pinfunction "2_2") (pintype "passive"))
      (node (ref "U4003") (pin "34") (pinfunction "IREF_34") (pintype "bidirectional"))
    )
    (net (code "27") (name "/DRIVER_IREF_1") (class "Default")
      (node (ref "R4044") (pin "2") (pinfunction "2_2") (pintype "passive"))
      (node (ref "U4004") (pin "34") (pinfunction "IREF_34") (pintype "bidirectional"))
    )
    (net (code "28") (name "/DRIVER_IREF_2") (class "Default")
      (node (ref "R4045") (pin "2") (pinfunction "2_2") (pintype "passive"))
      (node (ref "U4005") (pin "34") (pinfunction "IREF_34") (pintype "bidirectional"))
    )
    (net (code "29") (name "/DRIVER_IREF_3") (class "Default")
      (node (ref "R4046") (pin "2") (pinfunction "2_2") (pintype "passive"))
      (node (ref "U4006") (pin "34") (pinfunction "IREF_34") (pintype "bidirectional"))
    )
    (net (code "30") (name "/DRIVER_IREF_4") (class "Default")
      (node (ref "R4047") (pin "2") (pinfunction "2_2") (pintype "passive"))
      (node (ref "U4007") (pin "34") (pinfunction "IREF_34") (pintype "bidirectional"))
    )
    (net (code "31") (name "/GATE_0") (class "Default")
      (node (ref "M4000") (pin "1") (pinfunction "Gate_1") (pintype "passive"))
      (node (ref "R4007") (pin "2") (pinfunction "2_2") (pintype "passive"))
    )
    (net (code "32") (name "/GATE_1") (class "Default")
      (node (ref "M4000") (pin "3") (pinfunction "Gate_3") (pintype "passive"))
      (node (ref "R4008") (pin "2") (pinfunction "2_2") (pintype "passive"))
    )
    (net (code "33") (name "/GATE_2") (class "Default")
      (node (ref "M4001") (pin "1") (pinfunction "Gate_1") (pintype "passive"))
      (node (ref "R4009") (pin "2") (pinfunction "2_2") (pintype "passive"))
    )
    (net (code "34") (name "/GATE_3") (class "Default")
      (node (ref "M4001") (pin "3") (pinfunction "Gate_3") (pintype "passive"))
      (node (ref "R4010") (pin "2") (pinfunction "2_2") (pintype "passive"))
    )
    (net (code "35") (name "/GATE_4") (class "Default")
      (node (ref "M4002") (pin "1") (pinfunction "Gate_1") (pintype "passive"))
      (node (ref "R4011") (pin "2") (pinfunction "2_2") (pintype "passive"))
    )
    (net (code "36") (name "/GATE_5") (class "Default")
      (node (ref "M4002") (pin "3") (pinfunction "Gate_3") (pintype "passive"))
      (node (ref "R4012") (pin "2") (pinfunction "2_2") (pintype "passive"))
    )
    (net (code "37") (name "/GATE_6") (class "Default")
      (node (ref "M4003") (pin "1") (pinfunction "Gate_1") (pintype "passive"))
      (node (ref "R4013") (pin "2") (pinfunction "2_2") (pintype "passive"))
    )
    (net (code "38") (name "/GATE_7") (class "Default")
      (node (ref "M4004") (pin "1") (pinfunction "Gate_1") (pintype "passive"))
      (node (ref "R4021") (pin "2") (pinfunction "2_2") (pintype "passive"))
    )
    (net (code "39") (name "/GATE_8") (class "Default")
      (node (ref "M4003") (pin "3") (pinfunction "Gate_3") (pintype "passive"))
      (node (ref "R4022") (pin "2") (pinfunction "2_2") (pintype "passive"))
    )
    (net (code "40") (name "/GATE_9") (class "Default")
      (node (ref "M4005") (pin "1") (pinfunction "Gate_1") (pintype "passive"))
      (node (ref "R4023") (pin "2") (pinfunction "2_2") (pintype "passive"))
    )
    (net (code "41") (name "/GATE_10") (class "Default")
      (node (ref "M4004") (pin "3") (pinfunction "Gate_3") (pintype "passive"))
      (node (ref "R4024") (pin "2") (pinfunction "2_2") (pintype "passive"))
    )
    (net (code "42") (name "/GATE_11") (class "Default")
      (node (ref "M4006") (pin "1") (pinfunction "Gate_1") (pintype "passive"))
      (node (ref "R4025") (pin "2") (pinfunction "2_2") (pintype "passive"))
    )
    (net (code "43") (name "/GATE_12") (class "Default")
      (node (ref "M4005") (pin "3") (pinfunction "Gate_3") (pintype "passive"))
      (node (ref "R4026") (pin "2") (pinfunction "2_2") (pintype "passive"))
    )
    (net (code "44") (name "/GATE_13") (class "Default")
      (node (ref "M4007") (pin "1") (pinfunction "Gate_1") (pintype "passive"))
      (node (ref "R4027") (pin "2") (pinfunction "2_2") (pintype "passive"))
    )
    (net (code "45") (name "/GATE_14") (class "Default")
      (node (ref "M4008") (pin "1") (pinfunction "Gate_1") (pintype "passive"))
      (node (ref "R4035") (pin "2") (pinfunction "2_2") (pintype "passive"))
    )
    (net (code "46") (name "/GATE_15") (class "Default")
      (node (ref "M4006") (pin "3") (pinfunction "Gate_3") (pintype "passive"))
      (node (ref "R4036") (pin "2") (pinfunction "2_2") (pintype "passive"))
    )
    (net (code "47") (name "/GATE_16") (class "Default")
      (node (ref "M4009") (pin "1") (pinfunction "Gate_1") (pintype "passive"))
      (node (ref "R4037") (pin "2") (pinfunction "2_2") (pintype "passive"))
    )
    (net (code "48") (name "/GATE_17") (class "Default")
      (node (ref "M4007") (pin "3") (pinfunction "Gate_3") (pintype "passive"))
      (node (ref "R4038") (pin "2") (pinfunction "2_2") (pintype "passive"))
    )
    (net (code "49") (name "/GATE_18") (class "Default")
      (node (ref "M4010") (pin "1") (pinfunction "Gate_1") (pintype "passive"))
      (node (ref "R4039") (pin "2") (pinfunction "2_2") (pintype "passive"))
    )
    (net (code "50") (name "/GATE_19") (class "Default")
      (node (ref "M4008") (pin "3") (pinfunction "Gate_3") (pintype "passive"))
      (node (ref "R4040") (pin "2") (pinfunction "2_2") (pintype "passive"))
    )
    (net (code "51") (name "/GATE_20") (class "Default")
      (node (ref "M4011") (pin "1") (pinfunction "Gate_1") (pintype "passive"))
      (node (ref "R4041") (pin "2") (pinfunction "2_2") (pintype "passive"))
    )
    (net (code "52") (name "/MATRIX_COL_B0") (class "Default")
      (node (ref "U4003") (pin "9") (pinfunction "OUTB0_9") (pintype "output"))
    )
    (net (code "53") (name "/MATRIX_COL_B1") (class "Default")
      (node (ref "U4003") (pin "12") (pinfunction "OUTB1_12") (pintype "output"))
    )
    (net (code "54") (name "/MATRIX_COL_B2") (class "Default")
      (node (ref "U4003") (pin "15") (pinfunction "OUTB2_15") (pintype "output"))
    )
    (net (code "55") (name "/MATRIX_COL_B3") (class "Default")
      (node (ref "U4003") (pin "18") (pinfunction "OUTB3_18") (pintype "output"))
    )
    (net (code "56") (name "/MATRIX_COL_B4") (class "Default")
      (node (ref "U4003") (pin "21") (pinfunction "OUTB4_21") (pintype "output"))
    )
    (net (code "57") (name "/MATRIX_COL_B5") (class "Default")
      (node (ref "U4003") (pin "24") (pinfunction "OUTB5_24") (pintype "output"))
    )
    (net (code "58") (name "/MATRIX_COL_B6") (class "Default")
      (node (ref "U4003") (pin "27") (pinfunction "OUTB6_27") (pintype "output"))
    )
    (net (code "59") (name "/MATRIX_COL_B7") (class "Default")
      (node (ref "U4004") (pin "9") (pinfunction "OUTB0_9") (pintype "output"))
    )
    (net (code "60") (name "/MATRIX_COL_B8") (class "Default")
      (node (ref "U4004") (pin "12") (pinfunction "OUTB1_12") (pintype "output"))
    )
    (net (code "61") (name "/MATRIX_COL_B9") (class "Default")
      (node (ref "U4004") (pin "15") (pinfunction "OUTB2_15") (pintype "output"))
    )
    (net (code "62") (name "/MATRIX_COL_B10") (class "Default")
      (node (ref "U4004") (pin "18") (pinfunction "OUTB3_18") (pintype "output"))
    )
    (net (code "63") (name "/MATRIX_COL_B11") (class "Default")
      (node (ref "U4004") (pin "21") (pinfunction "OUTB4_21") (pintype "output"))
    )
    (net (code "64") (name "/MATRIX_COL_B12") (class "Default")
      (node (ref "U4004") (pin "24") (pinfunction "OUTB5_24") (pintype "output"))
    )
    (net (code "65") (name "/MATRIX_COL_B13") (class "Default")
      (node (ref "U4004") (pin "27") (pinfunction "OUTB6_27") (pintype "output"))
    )
    (net (code "66") (name "/MATRIX_COL_B14") (class "Default")
      (node (ref "U4005") (pin "9") (pinfunction "OUTB0_9") (pintype "output"))
    )
    (net (code "67") (name "/MATRIX_COL_B15") (class "Default")
      (node (ref "U4005") (pin "12") (pinfunction "OUTB1_12") (pintype "output"))
    )
    (net (code "68") (name "/MATRIX_COL_B16") (class "Default")
      (node (ref "U4005") (pin "15") (pinfunction "OUTB2_15") (pintype "output"))
    )
    (net (code "69") (name "/MATRIX_COL_B17") (class "Default")
      (node (ref "U4005") (pin "18") (pinfunction "OUTB3_18") (pintype "output"))
    )
    (net (code "70") (name "/MATRIX_COL_B18") (class "Default")
      (node (ref "U4005") (pin "21") (pinfunction "OUTB4_21") (pintype "output"))
    )
    (net (code "71") (name "/MATRIX_COL_B19") (class "Default")
      (node (ref "U4005") (pin "24") (pinfunction "OUTB5_24") (pintype "output"))
    )
    (net (code "72") (name "/MATRIX_COL_B20") (class "Default")
      (node (ref "U4005") (pin "27") (pinfunction "OUTB6_27") (pintype "output"))
    )
    (net (code "73") (name "/MATRIX_COL_B21") (class "Default")
      (node (ref "U4006") (pin "9") (pinfunction "OUTB0_9") (pintype "output"))
    )
    (net (code "74") (name "/MATRIX_COL_B22") (class "Default")
      (node (ref "U4006") (pin "12") (pinfunction "OUTB1_12") (pintype "output"))
    )
    (net (code "75") (name "/MATRIX_COL_B23") (class "Default")
      (node (ref "U4006") (pin "15") (pinfunction "OUTB2_15") (pintype "output"))
    )
    (net (code "76") (name "/MATRIX_COL_B24") (class "Default")
      (node (ref "U4006") (pin "18") (pinfunction "OUTB3_18") (pintype "output"))
    )
    (net (code "77") (name "/MATRIX_COL_B25") (class "Default")
      (node (ref "U4006") (pin "21") (pinfunction "OUTB4_21") (pintype "output"))
    )
    (net (code "78") (name "/MATRIX_COL_B26") (class "Default")
      (node (ref "U4006") (pin "24") (pinfunction "OUTB5_24") (pintype "output"))
    )
    (net (code "79") (name "/MATRIX_COL_B27") (class "Default")
      (node (ref "U4006") (pin "27") (pinfunction "OUTB6_27") (pintype "output"))
    )
    (net (code "80") (name "/MATRIX_COL_B28") (class "Default")
      (node (ref "U4007") (pin "9") (pinfunction "OUTB0_9") (pintype "output"))
    )
    (net (code "81") (name "/MATRIX_COL_B29") (class "Default")
      (node (ref "U4007") (pin "12") (pinfunction "OUTB1_12") (pintype "output"))
    )
    (net (code "82") (name "/MATRIX_COL_B30") (class "Default")
      (node (ref "U4007") (pin "15") (pinfunction "OUTB2_15") (pintype "output"))
    )
    (net (code "83") (name "/MATRIX_COL_B31") (class "Default")
      (node (ref "U4007") (pin "18") (pinfunction "OUTB3_18") (pintype "output"))
    )
    (net (code "84") (name "/MATRIX_COL_B32") (class "Default")
      (node (ref "U4007") (pin "21") (pinfunction "OUTB4_21") (pintype "output"))
    )
    (net (code "85") (name "/MATRIX_COL_B33") (class "Default")
      (node (ref "U4007") (pin "24") (pinfunction "OUTB5_24") (pintype "output"))
    )
    (net (code "86") (name "/MATRIX_COL_B34") (class "Default")
      (node (ref "U4007") (pin "27") (pinfunction "OUTB6_27") (pintype "output"))
    )
    (net (code "92") (name "/MATRIX_COL_G0") (class "Default")
      (node (ref "U4003") (pin "7") (pinfunction "OUTG0_7") (pintype "output"))
    )
    (net (code "93") (name "/MATRIX_COL_G1") (class "Default")
      (node (ref "U4003") (pin "10") (pinfunction "OUTG1_10") (pintype "output"))
    )
    (net (code "94") (name "/MATRIX_COL_G2") (class "Default")
      (node (ref "U4003") (pin "13") (pinfunction "OUTG2_13") (pintype "output"))
    )
    (net (code "95") (name "/MATRIX_COL_G3") (class "Default")
      (node (ref "U4003") (pin "16") (pinfunction "OUTG3_16") (pintype "output"))
    )
    (net (code "96") (name "/MATRIX_COL_G4") (class "Default")
      (node (ref "U4003") (pin "23") (pinfunction "OUTG4_23") (pintype "output"))
    )
    (net (code "97") (name "/MATRIX_COL_G5") (class "Default")
      (node (ref "U4003") (pin "26") (pinfunction "OUTG5_26") (pintype "output"))
    )
    (net (code "98") (name "/MATRIX_COL_G6") (class "Default")
      (node (ref "U4003") (pin "29") (pinfunction "OUTG6_29") (pintype "output"))
    )
    (net (code "99") (name "/MATRIX_COL_G7") (class "Default")
      (node (ref "U4004") (pin "7") (pinfunction "OUTG0_7") (pintype "output"))
    )
    (net (code "100") (name "/MATRIX_COL_G8") (class "Default")
      (node (ref "U4004") (pin "10") (pinfunction "OUTG1_10") (pintype "output"))
    )
    (net (code "101") (name "/MATRIX_COL_G9") (class "Default")
      (node (ref "U4004") (pin "13") (pinfunction "OUTG2_13") (pintype "output"))
    )
    (net (code "102") (name "/MATRIX_COL_G10") (class "Default")
      (node (ref "U4004") (pin "16") (pinfunction "OUTG3_16") (pintype "output"))
    )
    (net (code "103") (name "/MATRIX_COL_G11") (class "Default")
      (node (ref "U4004") (pin "23") (pinfunction "OUTG4_23") (pintype "output"))
    )
    (net (code "104") (name "/MATRIX_COL_G12") (class "Default")
      (node (ref "U4004") (pin "26") (pinfunction "OUTG5_26") (pintype "output"))
    )
    (net (code "105") (name "/MATRIX_COL_G13") (class "Default")
      (node (ref "U4004") (pin "29") (pinfunction "OUTG6_29") (pintype "output"))
    )
    (net (code "106") (name "/MATRIX_COL_G14") (class "Default")
      (node (ref "U4005") (pin "7") (pinfunction "OUTG0_7") (pintype "output"))
    )
    (net (code "107") (name "/MATRIX_COL_G15") (class "Default")
      (node (ref "U4005") (pin "10") (pinfunction "OUTG1_10") (pintype "output"))
    )
    (net (code "108") (name "/MATRIX_COL_G16") (class "Default")
      (node (ref "U4005") (pin "13") (pinfunction "OUTG2_13") (pintype "output"))
    )
    (net (code "109") (name "/MATRIX_COL_G17") (class "Default")
      (node (ref "U4005") (pin "16") (pinfunction "OUTG3_16") (pintype "output"))
    )
    (net (code "110") (name "/MATRIX_COL_G18") (class "Default")
      (node (ref "U4005") (pin "23") (pinfunction "OUTG4_23") (pintype "output"))
    )
    (net (code "111") (name "/MATRIX_COL_G19") (class "Default")
      (node (ref "U4005") (pin "26") (pinfunction "OUTG5_26") (pintype "output"))
    )
    (net (code "112") (name "/MATRIX_COL_G20") (class "Default")
      (node (ref "U4005") (pin "29") (pinfunction "OUTG6_29") (pintype "output"))
    )
    (net (code "113") (name "/MATRIX_COL_G21") (class "Default")
      (node (ref "U4006") (pin "7") (pinfunction "OUTG0_7") (pintype "output"))
    )
    (net (code "114") (name "/MATRIX_COL_G22") (class "Default")
      (node (ref "U4006") (pin "10") (pinfunction "OUTG1_10") (pintype "output"))
    )
    (net (code "115") (name "/MATRIX_COL_G23") (class "Default")
      (node (ref "U4006") (pin "13") (pinfunction "OUTG2_13") (pintype "output"))
    )
    (net (code "116") (name "/MATRIX_COL_G24") (class "Default")
      (node (ref "U4006") (pin "16") (pinfunction "OUTG3_16") (pintype "output"))
    )
    (net (code "117") (name "/MATRIX_COL_G25") (class "Default")
      (node (ref "U4006") (pin "23") (pinfunction "OUTG4_23") (pintype "output"))
    )
    (net (code "118") (name "/MATRIX_COL_G26") (class "Default")
      (node (ref "U4006") (pin "26") (pinfunction "OUTG5_26") (pintype "output"))
    )
    (net (code "119") (name "/MATRIX_COL_G27") (class "Default")
      (node (ref "U4006") (pin "29") (pinfunction "OUTG6_29") (pintype "output"))
    )
    (net (code "120") (name "/MATRIX_COL_G28") (class "Default")
      (node (ref "U4007") (pin "7") (pinfunction "OUTG0_7") (pintype "output"))
    )
    (net (code "121") (name "/MATRIX_COL_G29") (class "Default")
      (node (ref "U4007") (pin "10") (pinfunction "OUTG1_10") (pintype "output"))
    )
    (net (code "122") (name "/MATRIX_COL_G30") (class "Default")
      (node (ref "U4007") (pin "13") (pinfunction "OUTG2_13") (pintype "output"))
    )
    (net (code "123") (name "/MATRIX_COL_G31") (class "Default")
      (node (ref "U4007") (pin "16") (pinfunction "OUTG3_16") (pintype "output"))
    )
    (net (code "124") (name "/MATRIX_COL_G32") (class "Default")
      (node (ref "U4007") (pin "23") (pinfunction "OUTG4_23") (pintype "output"))
    )
    (net (code "125") (name "/MATRIX_COL_G33") (class "Default")
      (node (ref "U4007") (pin "26") (pinfunction "OUTG5_26") (pintype "output"))
    )
    (net (code "126") (name "/MATRIX_COL_G34") (class "Default")
      (node (ref "U4007") (pin "29") (pinfunction "OUTG6_29") (pintype "output"))
    )
    (net (code "132") (name "/MATRIX_COL_R0") (class "Default")
      (node (ref "U4003") (pin "8") (pinfunction "OUTR0_8") (pintype "output"))
    )
    (net (code "133") (name "/MATRIX_COL_R1") (class "Default")
      (node (ref "U4003") (pin "11") (pinfunction "OUTR1_11") (pintype "output"))
    )
    (net (code "134") (name "/MATRIX_COL_R2") (class "Default")
      (node (ref "U4003") (pin "14") (pinfunction "OUTR2_14") (pintype "output"))
    )
    (net (code "135") (name "/MATRIX_COL_R3") (class "Default")
      (node (ref "U4003") (pin "17") (pinfunction "OUTR3_17") (pintype "output"))
    )
    (net (code "136") (name "/MATRIX_COL_R4") (class "Default")
      (node (ref "U4003") (pin "22") (pinfunction "OUTR4_22") (pintype "output"))
    )
    (net (code "137") (name "/MATRIX_COL_R5") (class "Default")
      (node (ref "U4003") (pin "25") (pinfunction "OUTR5_25") (pintype "output"))
    )
    (net (code "138") (name "/MATRIX_COL_R6") (class "Default")
      (node (ref "U4003") (pin "28") (pinfunction "OUTR6_28") (pintype "output"))
    )
    (net (code "139") (name "/MATRIX_COL_R7") (class "Default")
      (node (ref "U4004") (pin "8") (pinfunction "OUTR0_8") (pintype "output"))
    )
    (net (code "140") (name "/MATRIX_COL_R8") (class "Default")
      (node (ref "U4004") (pin "11") (pinfunction "OUTR1_11") (pintype "output"))
    )
    (net (code "141") (name "/MATRIX_COL_R9") (class "Default")
      (node (ref "U4004") (pin "14") (pinfunction "OUTR2_14") (pintype "output"))
    )
    (net (code "142") (name "/MATRIX_COL_R10") (class "Default")
      (node (ref "U4004") (pin "17") (pinfunction "OUTR3_17") (pintype "output"))
    )
    (net (code "143") (name "/MATRIX_COL_R11") (class "Default")
      (node (ref "U4004") (pin "22") (pinfunction "OUTR4_22") (pintype "output"))
    )
    (net (code "144") (name "/MATRIX_COL_R12") (class "Default")
      (node (ref "U4004") (pin "25") (pinfunction "OUTR5_25") (pintype "output"))
    )
    (net (code "145") (name "/MATRIX_COL_R13") (class "Default")
      (node (ref "U4004") (pin "28") (pinfunction "OUTR6_28") (pintype "output"))
    )
    (net (code "146") (name "/MATRIX_COL_R14") (class "Default")
      (node (ref "U4005") (pin "8") (pinfunction "OUTR0_8") (pintype "output"))
    )
    (net (code "147") (name "/MATRIX_COL_R15") (class "Default")
      (node (ref "U4005") (pin "11") (pinfunction "OUTR1_11") (pintype "output"))
    )
    (net (code "148") (name "/MATRIX_COL_R16") (class "Default")
      (node (ref "U4005") (pin "14") (pinfunction "OUTR2_14") (pintype "output"))
    )
    (net (code "149") (name "/MATRIX_COL_R17") (class "Default")
      (node (ref "U4005") (pin "17") (pinfunction "OUTR3_17") (pintype "output"))
    )
    (net (code "150") (name "/MATRIX_COL_R18") (class "Default")
      (node (ref "U4005") (pin "22") (pinfunction "OUTR4_22") (pintype "output"))
    )
    (net (code "151") (name "/MATRIX_COL_R19") (class "Default")
      (node (ref "U4005") (pin "25") (pinfunction "OUTR5_25") (pintype "output"))
    )
    (net (code "152") (name "/MATRIX_COL_R20") (class "Default")
      (node (ref "U4005") (pin "28") (pinfunction "OUTR6_28") (pintype "output"))
    )
    (net (code "153") (name "/MATRIX_COL_R21") (class "Default")
      (node (ref "U4006") (pin "8") (pinfunction "OUTR0_8") (pintype "output"))
    )
    (net (code "154") (name "/MATRIX_COL_R22") (class "Default")
      (node (ref "U4006") (pin "11") (pinfunction "OUTR1_11") (pintype "output"))
    )
    (net (code "155") (name "/MATRIX_COL_R23") (class "Default")
      (node (ref "U4006") (pin "14") (pinfunction "OUTR2_14") (pintype "output"))
    )
    (net (code "156") (name "/MATRIX_COL_R24") (class "Default")
      (node (ref "U4006") (pin "17") (pinfunction "OUTR3_17") (pintype "output"))
    )
    (net (code "157") (name "/MATRIX_COL_R25") (class "Default")
      (node (ref "U4006") (pin "22") (pinfunction "OUTR4_22") (pintype "output"))
    )
    (net (code "158") (name "/MATRIX_COL_R26") (class "Default")
      (node (ref "U4006") (pin "25") (pinfunction "OUTR5_25") (pintype "output"))
    )
    (net (code "159") (name "/MATRIX_COL_R27") (class "Default")
      (node (ref "U4006") (pin "28") (pinfunction "OUTR6_28") (pintype "output"))
    )
    (net (code "160") (name "/MATRIX_COL_R28") (class "Default")
      (node (ref "U4007") (pin "8") (pinfunction "OUTR0_8") (pintype "output"))
    )
    (net (code "161") (name "/MATRIX_COL_R29") (class "Default")
      (node (ref "U4007") (pin "11") (pinfunction "OUTR1_11") (pintype "output"))
    )
    (net (code "162") (name "/MATRIX_COL_R30") (class "Default")
      (node (ref "U4007") (pin "14") (pinfunction "OUTR2_14") (pintype "output"))
    )
    (net (code "163") (name "/MATRIX_COL_R31") (class "Default")
      (node (ref "U4007") (pin "17") (pinfunction "OUTR3_17") (pintype "output"))
    )
    (net (code "164") (name "/MATRIX_COL_R32") (class "Default")
      (node (ref "U4007") (pin "22") (pinfunction "OUTR4_22") (pintype "output"))
    )
    (net (code "165") (name "/MATRIX_COL_R33") (class "Default")
      (node (ref "U4007") (pin "25") (pinfunction "OUTR5_25") (pintype "output"))
    )
    (net (code "166") (name "/MATRIX_COL_R34") (class "Default")
      (node (ref "U4007") (pin "28") (pinfunction "OUTR6_28") (pintype "output"))
    )
    (net (code "172") (name "/MATRIX_ROW_0") (class "Default")
      (node (ref "M4000") (pin "6") (pinfunction "Drain_6") (pintype "passive"))
    )
    (net (code "173") (name "/MATRIX_ROW_1") (class "Default")
      (node (ref "M4000") (pin "4") (pinfunction "Drain_4") (pintype "passive"))
    )
    (net (code "174") (name "/MATRIX_ROW_2") (class "Default")
      (node (ref "M4001") (pin "6") (pinfunction "Drain_6") (pintype "passive"))
    )
    (net (code "175") (name "/MATRIX_ROW_3") (class "Default")
      (node (ref "M4001") (pin "4") (pinfunction "Drain_4") (pintype "passive"))
    )
    (net (code "176") (name "/MATRIX_ROW_4") (class "Default")
      (node (ref "M4002") (pin "6") (pinfunction "Drain_6") (pintype "passive"))
    )
    (net (code "177") (name "/MATRIX_ROW_5") (class "Default")
      (node (ref "M4002") (pin "4") (pinfunction "Drain_4") (pintype "passive"))
    )
    (net (code "178") (name "/MATRIX_ROW_6") (class "Default")
      (node (ref "M4003") (pin "6") (pinfunction "Drain_6") (pintype "passive"))
    )
    (net (code "179") (name "/MATRIX_ROW_7") (class "Default")
      (node (ref "M4004") (pin "6") (pinfunction "Drain_6") (pintype "passive"))
    )
    (net (code "180") (name "/MATRIX_ROW_8") (class "Default")
      (node (ref "M4003") (pin "4") (pinfunction "Drain_4") (pintype "passive"))
    )
    (net (code "181") (name "/MATRIX_ROW_9") (class "Default")
      (node (ref "M4005") (pin "6") (pinfunction "Drain_6") (pintype "passive"))
    )
    (net (code "182") (name "/MATRIX_ROW_10") (class "Default")
      (node (ref "M4004") (pin "4") (pinfunction "Drain_4") (pintype "passive"))
    )
    (net (code "183") (name "/MATRIX_ROW_11") (class "Default")
      (node (ref "M4006") (pin "6") (pinfunction "Drain_6") (pintype "passive"))
    )
    (net (code "184") (name "/MATRIX_ROW_12") (class "Default")
      (node (ref "M4005") (pin "4") (pinfunction "Drain_4") (pintype "passive"))
    )
    (net (code "185") (name "/MATRIX_ROW_13") (class "Default")
      (node (ref "M4007") (pin "6") (pinfunction "Drain_6") (pintype "passive"))
    )
    (net (code "186") (name "/MATRIX_ROW_14") (class "Default")
      (node (ref "M4008") (pin "6") (pinfunction "Drain_6") (pintype "passive"))
    )
    (net (code "187") (name "/MATRIX_ROW_15") (class "Default")
      (node (ref "M4006") (pin "4") (pinfunction "Drain_4") (pintype "passive"))
    )
    (net (code "188") (name "/MATRIX_ROW_16") (class "Default")
      (node (ref "M4009") (pin "6") (pinfunction "Drain_6") (pintype "passive"))
    )
    (net (code "189") (name "/MATRIX_ROW_17") (class "Default")
      (node (ref "M4007") (pin "4") (pinfunction "Drain_4") (pintype "passive"))
    )
    (net (code "190") (name "/MATRIX_ROW_18") (class "Default")
      (node (ref "M4010") (pin "6") (pinfunction "Drain_6") (pintype "passive"))
    )
    (net (code "191") (name "/MATRIX_ROW_19") (class "Default")
      (node (ref "M4008") (pin "4") (pinfunction "Drain_4") (pintype "passive"))
    )
    (net (code "192") (name "/MATRIX_ROW_20") (class "Default")
      (node (ref "M4011") (pin "6") (pinfunction "Drain_6") (pintype "passive"))
    )
    (net (code "196") (name "/SHIFT_0") (class "Default")
      (node (ref "R4000") (pin "1") (pinfunction "1_1") (pintype "passive"))
      (node (ref "R4007") (pin "1") (pinfunction "1_1") (pintype "passive"))
      (node (ref "U4000") (pin "15") (pinfunction "QA_15") (pintype "output"))
    )
    (net (code "197") (name "/SHIFT_1") (class "Default")
      (node (ref "R4001") (pin "1") (pinfunction "1_1") (pintype "passive"))
      (node (ref "R4008") (pin "1") (pinfunction "1_1") (pintype "passive"))
      (node (ref "U4000") (pin "1") (pinfunction "QB_1") (pintype "output"))
    )
    (net (code "198") (name "/SHIFT_2") (class "Default")
      (node (ref "R4002") (pin "1") (pinfunction "1_1") (pintype "passive"))
      (node (ref "R4009") (pin "1") (pinfunction "1_1") (pintype "passive"))
      (node (ref "U4000") (pin "2") (pinfunction "QC_2") (pintype "output"))
    )
    (net (code "199") (name "/SHIFT_3") (class "Default")
      (node (ref "R4003") (pin "1") (pinfunction "1_1") (pintype "passive"))
      (node (ref "R4010") (pin "1") (pinfunction "1_1") (pintype "passive"))
      (node (ref "U4000") (pin "3") (pinfunction "QD_3") (pintype "output"))
    )
    (net (code "200") (name "/SHIFT_4") (class "Default")
      (node (ref "R4004") (pin "1") (pinfunction "1_1") (pintype "passive"))
      (node (ref "R4011") (pin "1") (pinfunction "1_1") (pintype "passive"))
      (node (ref "U4000") (pin "4") (pinfunction "QE_4") (pintype "output"))
    )
    (net (code "201") (name "/SHIFT_5") (class "Default")
      (node (ref "R4005") (pin "1") (pinfunction "1_1") (pintype "passive"))
      (node (ref "R4012") (pin "1") (pinfunction "1_1") (pintype "passive"))
      (node (ref "U4000") (pin "5") (pinfunction "QF_5") (pintype "output"))
    )
    (net (code "202") (name "/SHIFT_6") (class "Default")
      (node (ref "NT4008") (pin "2") (pinfunction "2_2") (pintype "passive"))
      (node (ref "R4006") (pin "1") (pinfunction "1_1") (pintype "passive"))
      (node (ref "R4013") (pin "1") (pinfunction "1_1") (pintype "passive"))
      (node (ref "U4000") (pin "6") (pinfunction "QG_6") (pintype "output"))
    )
    (net (code "203") (name "/SHIFT_7") (class "Default")
      (node (ref "R4014") (pin "1") (pinfunction "1_1") (pintype "passive"))
      (node (ref "R4021") (pin "1") (pinfunction "1_1") (pintype "passive"))
      (node (ref "U4001") (pin "15") (pinfunction "QA_15") (pintype "output"))
    )
    (net (code "204") (name "/SHIFT_8") (class "Default")
      (node (ref "R4015") (pin "1") (pinfunction "1_1") (pintype "passive"))
      (node (ref "R4022") (pin "1") (pinfunction "1_1") (pintype "passive"))
      (node (ref "U4001") (pin "1") (pinfunction "QB_1") (pintype "output"))
    )
    (net (code "205") (name "/SHIFT_9") (class "Default")
      (node (ref "R4016") (pin "1") (pinfunction "1_1") (pintype "passive"))
      (node (ref "R4023") (pin "1") (pinfunction "1_1") (pintype "passive"))
      (node (ref "U4001") (pin "2") (pinfunction "QC_2") (pintype "output"))
    )
    (net (code "206") (name "/SHIFT_10") (class "Default")
      (node (ref "R4017") (pin "1") (pinfunction "1_1") (pintype "passive"))
      (node (ref "R4024") (pin "1") (pinfunction "1_1") (pintype "passive"))
      (node (ref "U4001") (pin "3") (pinfunction "QD_3") (pintype "output"))
    )
    (net (code "207") (name "/SHIFT_11") (class "Default")
      (node (ref "R4018") (pin "1") (pinfunction "1_1") (pintype "passive"))
      (node (ref "R4025") (pin "1") (pinfunction "1_1") (pintype "passive"))
      (node (ref "U4001") (pin "4") (pinfunction "QE_4") (pintype "output"))
    )
    (net (code "208") (name "/SHIFT_12") (class "Default")
      (node (ref "R4019") (pin "1") (pinfunction "1_1") (pintype "passive"))
      (node (ref "R4026") (pin "1") (pinfunction "1_1") (pintype "passive"))
      (node (ref "U4001") (pin "5") (pinfunction "QF_5") (pintype "output"))
    )
    (net (code "209") (name "/SHIFT_13") (class "Default")
      (node (ref "NT4009") (pin "2") (pinfunction "2_2") (pintype "passive"))
      (node (ref "R4020") (pin "1") (pinfunction "1_1") (pintype "passive"))
      (node (ref "R4027") (pin "1") (pinfunction "1_1") (pintype "passive"))
      (node (ref "U4001") (pin "6") (pinfunction "QG_6") (pintype "output"))
    )
    (net (code "210") (name "/SHIFT_14") (class "Default")
      (node (ref "R4028") (pin "1") (pinfunction "1_1") (pintype "passive"))
      (node (ref "R4035") (pin "1") (pinfunction "1_1") (pintype "passive"))
      (node (ref "U4002") (pin "15") (pinfunction "QA_15") (pintype "output"))
    )
    (net (code "211") (name "/SHIFT_15") (class "Default")
      (node (ref "R4029") (pin "1") (pinfunction "1_1") (pintype "passive"))
      (node (ref "R4036") (pin "1") (pinfunction "1_1") (pintype "passive"))
      (node (ref "U4002") (pin "1") (pinfunction "QB_1") (pintype "output"))
    )
    (net (code "212") (name "/SHIFT_16") (class "Default")
      (node (ref "R4030") (pin "1") (pinfunction "1_1") (pintype "passive"))
      (node (ref "R4037") (pin "1") (pinfunction "1_1") (pintype "passive"))
      (node (ref "U4002") (pin "2") (pinfunction "QC_2") (pintype "output"))
    )
    (net (code "213") (name "/SHIFT_17") (class "Default")
      (node (ref "R4031") (pin "1") (pinfunction "1_1") (pintype "passive"))
      (node (ref "R4038") (pin "1") (pinfunction "1_1") (pintype "passive"))
      (node (ref "U4002") (pin "3") (pinfunction "QD_3") (pintype "output"))
    )
    (net (code "214") (name "/SHIFT_18") (class "Default")
      (node (ref "R4032") (pin "1") (pinfunction "1_1") (pintype "passive"))
      (node (ref "R4039") (pin "1") (pinfunction "1_1") (pintype "passive"))
      (node (ref "U4002") (pin "4") (pinfunction "QE_4") (pintype "output"))
    )
    (net (code "215") (name "/SHIFT_19") (class "Default")
      (node (ref "R4033") (pin "1") (pinfunction "1_1") (pintype "passive"))
      (node (ref "R4040") (pin "1") (pinfunction "1_1") (pintype "passive"))
      (node (ref "U4002") (pin "5") (pinfunction "QF_5") (pintype "output"))
    )
    (net (code "216") (name "/SHIFT_20") (class "Default")
      (node (ref "R4034") (pin "1") (pinfunction "1_1") (pintype "passive"))
      (node (ref "R4041") (pin "1") (pinfunction "1_1") (pintype "passive"))
      (node (ref "U4002") (pin "6") (pinfunction "QG_6") (pintype "output"))
    )
    (net (code "217") (name "/SHIFT_CLK") (class "Default")
      (node (ref "U4000") (pin "11") (pinfunction "SRCLK_11") (pintype "input"))
      (node (ref "U4000") (pin "12") (pinfunction "RCLK_12") (pintype "input"))
      (node (ref "U4001") (pin "11") (pinfunction "SRCLK_11") (pintype "input"))
      (node (ref "U4001") (pin "12") (pinfunction "RCLK_12") (pintype "input"))
      (node (ref "U4002") (pin "11") (pinfunction "SRCLK_11") (pintype "input"))
      (node (ref "U4002") (pin "12") (pinfunction "RCLK_12") (pintype "input"))
    )
    (net (code "218") (name "/SHIFT_SER_0") (class "Default")
      (node (ref "U4000") (pin "14") (pinfunction "SER_14") (pintype "input"))
    )
    (net (code "219") (name "/SHIFT_SER_1") (class "Default")
      (node (ref "NT4008") (pin "1") (pinfunction "1_1") (pintype "passive"))
      (node (ref "U4001") (pin "14") (pinfunction "SER_14") (pintype "input"))
    )
    (net (code "220") (name "/SHIFT_SER_2") (class "Default")
      (node (ref "NT4009") (pin "1") (pinfunction "1_1") (pintype "passive"))
      (node (ref "U4002") (pin "14") (pinfunction "SER_14") (pintype "input"))
    )
    (net (code "221") (name "/~DRIVER_XBLNK") (class "Default")
      (node (ref "U4003") (pin "36") (pinfunction "~XBLNK_36") (pintype "input"))
      (node (ref "U4004") (pin "36") (pinfunction "~XBLNK_36") (pintype "input"))
      (node (ref "U4005") (pin "36") (pinfunction "~XBLNK_36") (pintype "input"))
      (node (ref "U4006") (pin "36") (pinfunction "~XBLNK_36") (pintype "input"))
      (node (ref "U4007") (pin "36") (pinfunction "~XBLNK_36") (pintype "input"))
    )
    (net (code "222") (name "/~SHIFT_CLR") (class "Default")
      (node (ref "R4042") (pin "1") (pinfunction "1_1") (pintype "passive"))
      (node (ref "U4000") (pin "10") (pinfunction "~SRCLR_10") (pintype "input"))
      (node (ref "U4000") (pin "13") (pinfunction "~RCLR_13") (pintype "input"))
      (node (ref "U4001") (pin "10") (pinfunction "~SRCLR_10") (pintype "input"))
      (node (ref "U4001") (pin "13") (pinfunction "~RCLR_13") (pintype "input"))
      (node (ref "U4002") (pin "10") (pinfunction "~SRCLR_10") (pintype "input"))
      (node (ref "U4002") (pin "13") (pinfunction "~RCLR_13") (pintype "input"))
    )
    (net (code "223") (name "GND") (class "Default")
      (node (ref "C4000") (pin "1") (pinfunction "1_1") (pintype "passive"))
      (node (ref "C4001") (pin "1") (pinfunction "1_1") (pintype "passive"))
      (node (ref "C4002") (pin "1") (pinfunction "1_1") (pintype "passive"))
      (node (ref "C4003") (pin "1") (pinfunction "1_1") (pintype "passive"))
      (node (ref "C4004") (pin "1") (pinfunction "1_1") (pintype "passive"))
      (node (ref "C4005") (pin "1") (pinfunction "1_1") (pintype "passive"))
      (node (ref "C4006") (pin "1") (pinfunction "1_1") (pintype "passive"))
      (node (ref "C4007") (pin "1") (pinfunction "1_1") (pintype "passive"))
      (node (ref "R4043") (pin "1") (pinfunction "1_1") (pintype "passive"))
      (node (ref "R4044") (pin "1") (pinfunction "1_1") (pintype "passive"))
      (node (ref "R4045") (pin "1") (pinfunction "1_1") (pintype "passive"))
      (node (ref "R4046") (pin "1") (pinfunction "1_1") (pintype "passive"))
      (node (ref "R4047") (pin "1") (pinfunction "1_1") (pintype "passive"))
      (node (ref "U4000") (pin "8") (pinfunction "GND_8") (pintype "power_in"))
      (node (ref "U4001") (pin "8") (pinfunction "GND_8") (pintype "power_in"))
      (node (ref "U4002") (pin "8") (pinfunction "GND_8") (pintype "power_in"))
      (node (ref "U4003") (pin "33") (pinfunction "GND_33") (pintype "power_in"))
      (node (ref "U4003") (pin "39") (pinfunction "PAD_39") (pintype "power_in"))
      (node (ref "U4004") (pin "33") (pinfunction "GND_33") (pintype "power_in"))
      (node (ref "U4004") (pin "39") (pinfunction "PAD_39") (pintype "power_in"))
      (node (ref "U4005") (pin "33") (pinfunction "GND_33") (pintype "power_in"))
      (node (ref "U4005") (pin "39") (pinfunction "PAD_39") (pintype "power_in"))
      (node (ref "U4006") (pin "33") (pinfunction "GND_33") (pintype "power_in"))
      (node (ref "U4006") (pin "39") (pinfunction "PAD_39") (pintype "power_in"))
      (node (ref "U4007") (pin "33") (pinfunction "GND_33") (pintype "power_in"))
      (node (ref "U4007") (pin "39") (pinfunction "PAD_39") (pintype "power_in"))
    )
    (net (code "224") (name "VLED") (class "Default")
      (node (ref "M4000") (pin "2") (pinfunction "Source_2") (pintype "passive"))
      (node (ref "M4000") (pin "5") (pinfunction "Source_5") (pintype "passive"))
      (node (ref "M4001") (pin "2") (pinfunction "Source_2") (pintype "passive"))
      (node (ref "M4001") (pin "5") (pinfunction "Source_5") (pintype "passive"))
      (node (ref "M4002") (pin "2") (pinfunction "Source_2") (pintype "passive"))
      (node (ref "M4002") (pin "5") (pinfunction "Source_5") (pintype "passive"))
      (node (ref "M4003") (pin "2") (pinfunction "Source_2") (pintype "passive"))
      (node (ref "M4003") (pin "5") (pinfunction "Source_5") (pintype "passive"))
      (node (ref "M4004") (pin "2") (pinfunction "Source_2") (pintype "passive"))
      (node (ref "M4004") (pin "5") (pinfunction "Source_5") (pintype "passive"))
      (node (ref "M4005") (pin "2") (pinfunction "Source_2") (pintype "passive"))
      (node (ref "M4005") (pin "5") (pinfunction "Source_5") (pintype "passive"))
      (node (ref "M4006") (pin "2") (pinfunction "Source_2") (pintype "passive"))
      (node (ref "M4006") (pin "5") (pinfunction "Source_5") (pintype "passive"))
      (node (ref "M4007") (pin "2") (pinfunction "Source_2") (pintype "passive"))
      (node (ref "M4007") (pin "5") (pinfunction "Source_5") (pintype "passive"))
      (node (ref "M4008") (pin "2") (pinfunction "Source_2") (pintype "passive"))
      (node (ref "M4008") (pin "5") (pinfunction "Source_5") (pintype "passive"))
      (node (ref "M4009") (pin "5") (pinfunction "Source_5") (pintype "passive"))
      (node (ref "M4010") (pin "5") (pinfunction "Source_5") (pintype "passive"))
      (node (ref "M4011") (pin "5") (pinfunction "Source_5") (pintype "passive"))
      (node (ref "R4000") (pin "2") (pinfunction "2_2") (pintype "passive"))
      (node (ref "R4001") (pin "2") (pinfunction "2_2") (pintype "passive"))
      (node (ref "R4002") (pin "2") (pinfunction "2_2") (pintype "passive"))
      (node (ref "R4003") (pin "2") (pinfunction "2_2") (pintype "passive"))
      (node (ref "R4004") (pin "2") (pinfunction "2_2") (pintype "passive"))
      (node (ref "R4005") (pin "2") (pinfunction "2_2") (pintype "passive"))
      (node (ref "R4006") (pin "2") (pinfunction "2_2") (pintype "passive"))
      (node (ref "R4014") (pin "2") (pinfunction "2_2") (pintype "passive"))
      (node (ref "R4015") (pin "2") (pinfunction "2_2") (pintype "passive"))
      (node (ref "R4016") (pin "2") (pinfunction "2_2") (pintype "passive"))
      (node (ref "R4017") (pin "2") (pinfunction "2_2") (pintype "passive"))
      (node (ref "R4018") (pin "2") (pinfunction "2_2") (pintype "passive"))
      (node (ref "R4019") (pin "2") (pinfunction "2_2") (pintype "passive"))
      (node (ref "R4020") (pin "2") (pinfunction "2_2") (pintype "passive"))
      (node (ref "R4028") (pin "2") (pinfunction "2_2") (pintype "passive"))
      (node (ref "R4029") (pin "2") (pinfunction "2_2") (pintype "passive"))
      (node (ref "R4030") (pin "2") (pinfunction "2_2") (pintype "passive"))
      (node (ref "R4031") (pin "2") (pinfunction "2_2") (pintype "passive"))
      (node (ref "R4032") (pin "2") (pinfunction "2_2") (pintype "passive"))
      (node (ref "R4033") (pin "2") (pinfunction "2_2") (pintype "passive"))
      (node (ref "R4034") (pin "2") (pinfunction "2_2") (pintype "passive"))
    )
    (net (code "225") (name "unconnected-(U4000-QH'-Pad9)") (class "Default")
      (node (ref "U4000") (pin "9") (pinfunction "QH'_9") (pintype "output+no_connect"))
    )
    (net (code "226") (name "unconnected-(U4000-QH-Pad7)") (class "Default")
      (node (ref "U4000") (pin "7") (pinfunction "QH_7") (pintype "output+no_connect"))
    )
    (net (code "227") (name "unconnected-(U4001-QH'-Pad9)") (class "Default")
      (node (ref "U4001") (pin "9") (pinfunction "QH'_9") (pintype "output+no_connect"))
    )
    (net (code "228") (name "unconnected-(U4001-QH-Pad7)") (class "Default")
      (node (ref "U4001") (pin "7") (pinfunction "QH_7") (pintype "output+no_connect"))
    )
    (net (code "229") (name "unconnected-(U4002-QH'-Pad9)") (class "Default")
      (node (ref "U4002") (pin "9") (pinfunction "QH'_9") (pintype "output+no_connect"))
    )
    (net (code "230") (name "unconnected-(U4002-QH-Pad7)") (class "Default")
      (node (ref "U4002") (pin "7") (pinfunction "QH_7") (pintype "output+no_connect"))
    )
    (net (code "231") (name "unconnected-(U4003-OUTB7-Pad30)") (class "Default")
      (node (ref "U4003") (pin "30") (pinfunction "OUTB7_30") (pintype "output+no_connect"))
    )
    (net (code "232") (name "unconnected-(U4003-OUTG7-Pad32)") (class "Default")
      (node (ref "U4003") (pin "32") (pinfunction "OUTG7_32") (pintype "output+no_connect"))
    )
    (net (code "233") (name "unconnected-(U4003-OUTR7-Pad31)") (class "Default")
      (node (ref "U4003") (pin "31") (pinfunction "OUTR7_31") (pintype "output+no_connect"))
    )
    (net (code "234") (name "unconnected-(U4004-OUTB7-Pad30)") (class "Default")
      (node (ref "U4004") (pin "30") (pinfunction "OUTB7_30") (pintype "output+no_connect"))
    )
    (net (code "235") (name "unconnected-(U4004-OUTG7-Pad32)") (class "Default")
      (node (ref "U4004") (pin "32") (pinfunction "OUTG7_32") (pintype "output+no_connect"))
    )
    (net (code "236") (name "unconnected-(U4004-OUTR7-Pad31)") (class "Default")
      (node (ref "U4004") (pin "31") (pinfunction "OUTR7_31") (pintype "output+no_connect"))
    )
    (net (code "237") (name "unconnected-(U4005-OUTB7-Pad30)") (class "Default")
      (node (ref "U4005") (pin "30") (pinfunction "OUTB7_30") (pintype "output+no_connect"))
    )
    (net (code "238") (name "unconnected-(U4005-OUTG7-Pad32)") (class "Default")
      (node (ref "U4005") (pin "32") (pinfunction "OUTG7_32") (pintype "output+no_connect"))
    )
    (net (code "239") (name "unconnected-(U4005-OUTR7-Pad31)") (class "Default")
      (node (ref "U4005") (pin "31") (pinfunction "OUTR7_31") (pintype "output+no_connect"))
    )
    (net (code "240") (name "unconnected-(U4006-OUTB7-Pad30)") (class "Default")
      (node (ref "U4006") (pin "30") (pinfunction "OUTB7_30") (pintype "output+no_connect"))
    )
    (net (code "241") (name "unconnected-(U4006-OUTG7-Pad32)") (class "Default")
      (node (ref "U4006") (pin "32") (pinfunction "OUTG7_32") (pintype "output+no_connect"))
    )
    (net (code "242") (name "unconnected-(U4006-OUTR7-Pad31)") (class "Default")
      (node (ref "U4006") (pin "31") (pinfunction "OUTR7_31") (pintype "output+no_connect"))
    )
    (net (code "243") (name "unconnected-(U4007-DCSOUT-Pad20)") (class "Default")
      (node (ref "U4007") (pin "20") (pinfunction "DCSOUT_20") (pintype "output+no_connect"))
    )
    (net (code "244") (name "unconnected-(U4007-OUTB7-Pad30)") (class "Default")
      (node (ref "U4007") (pin "30") (pinfunction "OUTB7_30") (pintype "output+no_connect"))
    )
    (net (code "245") (name "unconnected-(U4007-OUTG7-Pad32)") (class "Default")
      (node (ref "U4007") (pin "32") (pinfunction "OUTG7_32") (pintype "output+no_connect"))
    )
    (net (code "246") (name "unconnected-(U4007-OUTR7-Pad31)") (class "Default")
      (node (ref "U4007") (pin "31") (pinfunction "OUTR7_31") (pintype "output+no_connect"))
    )
  )
)
